# tinylab_09-03-16.net
KiCad netlist of a schematic drawn in EAGLE
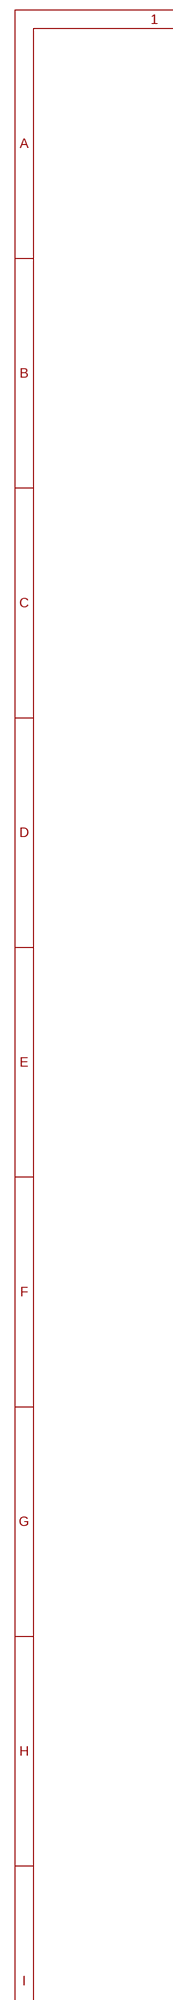
[diagram p0: schematic, sheet 1, part 1 of 2]
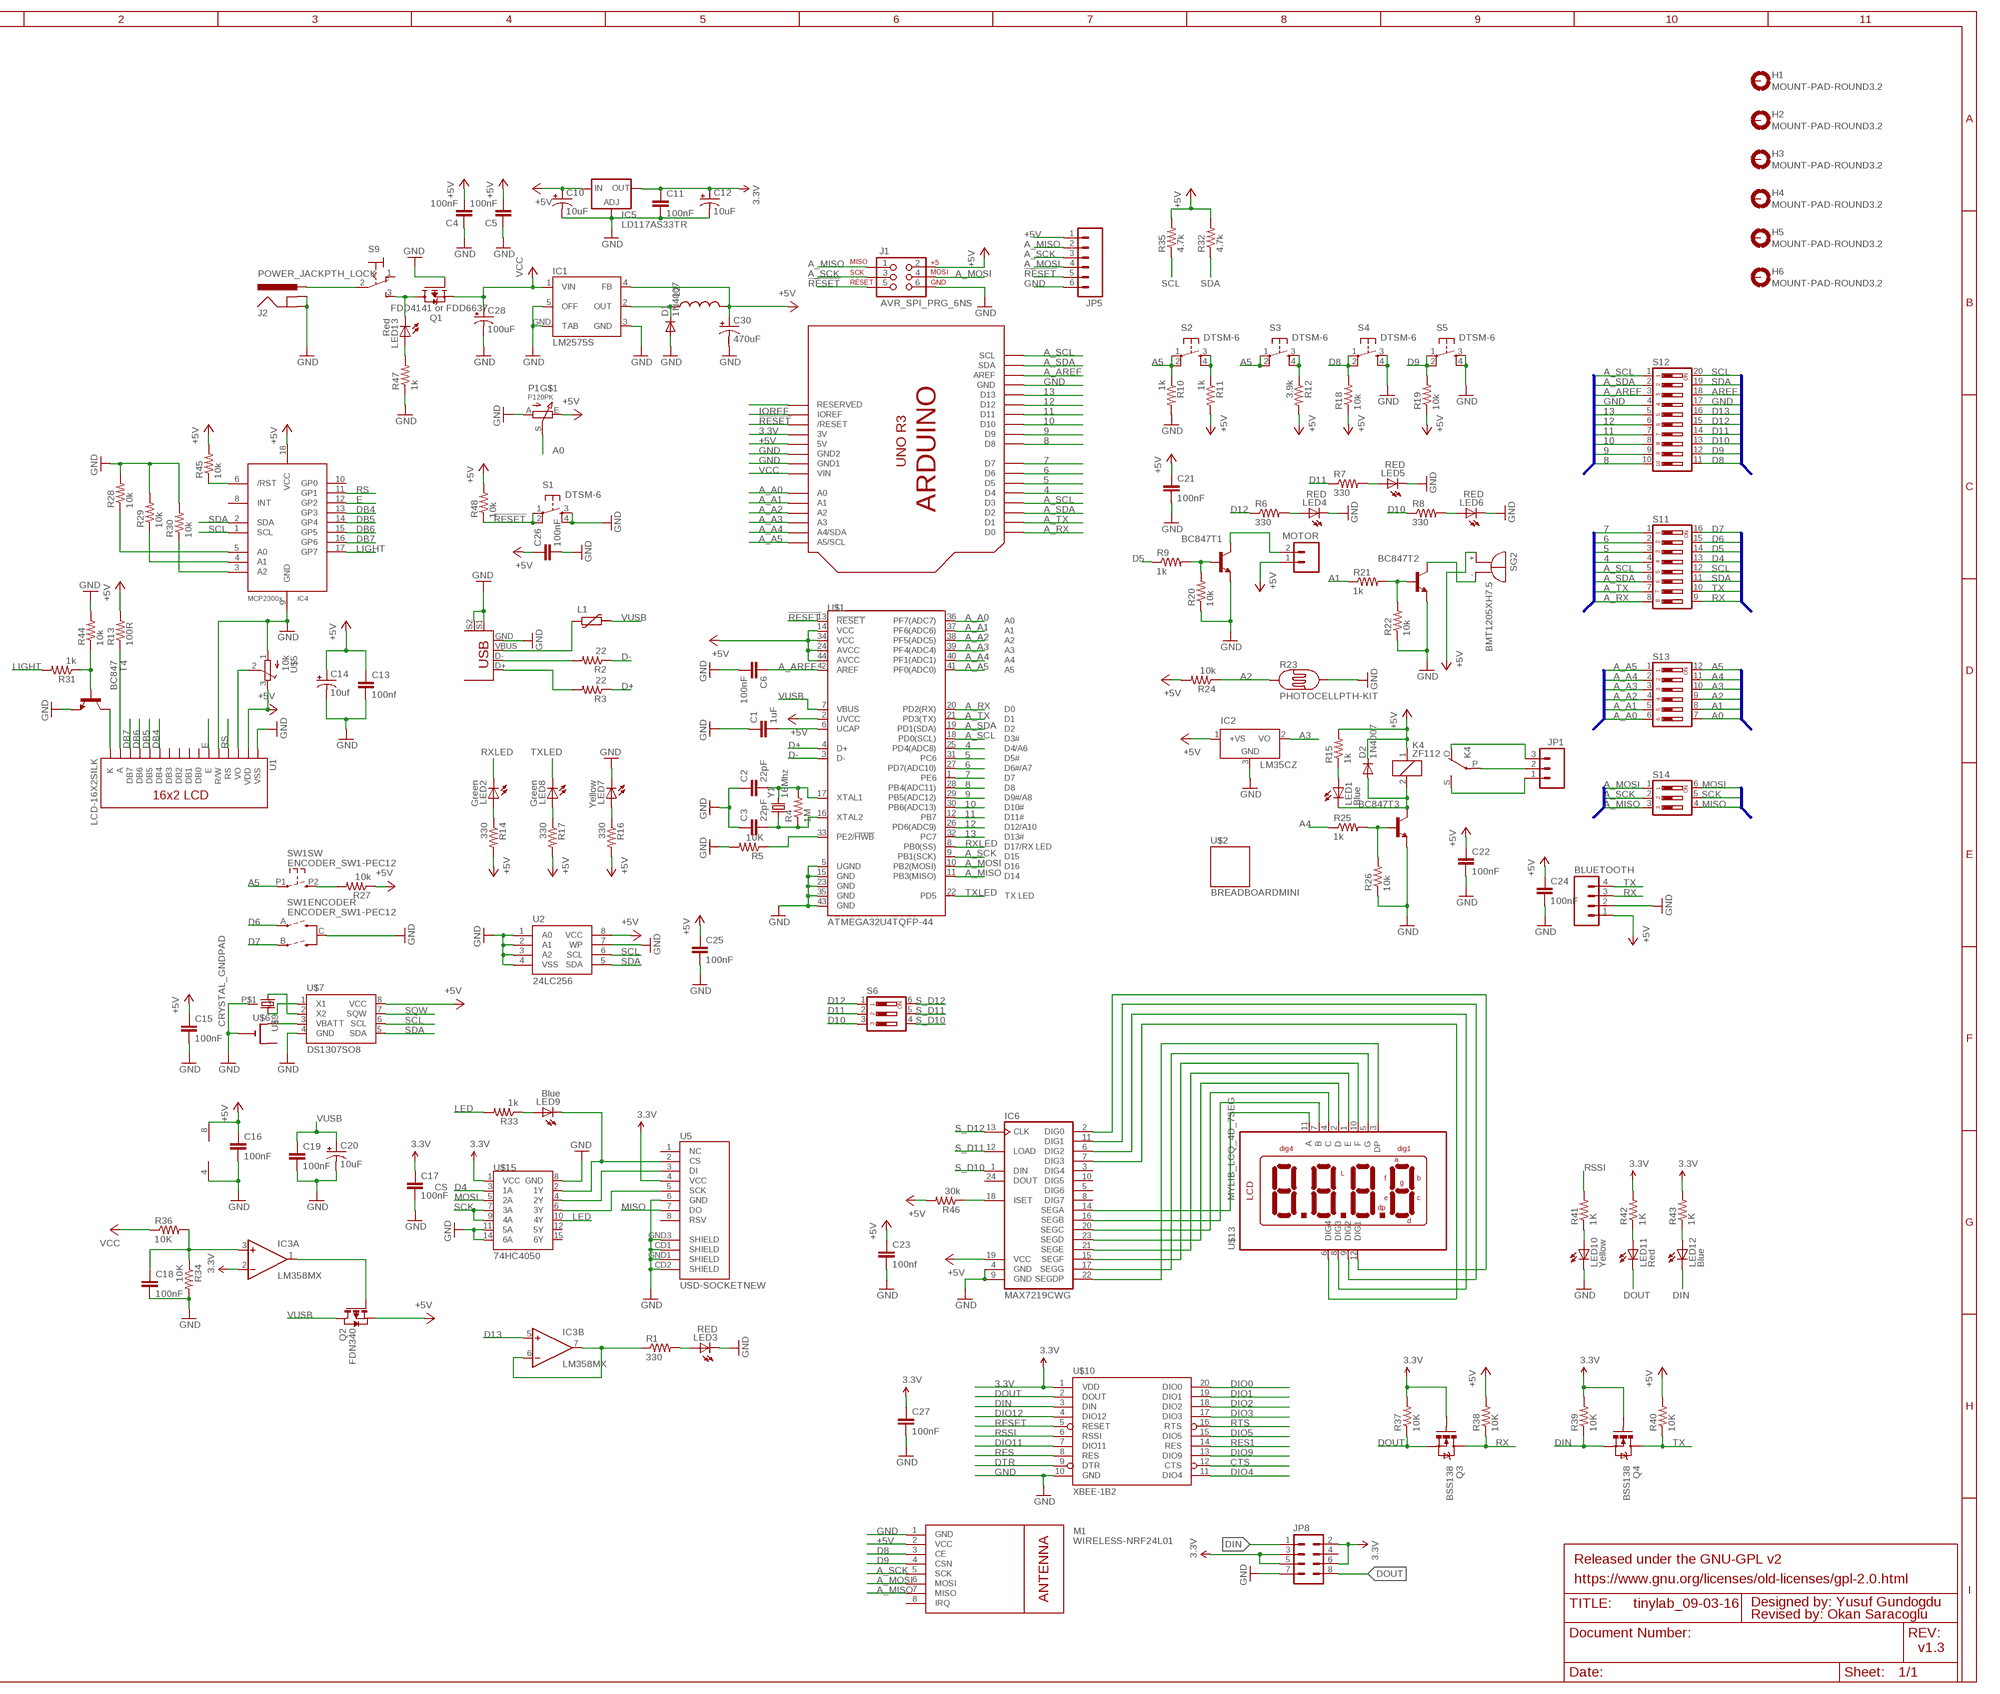
[diagram p1: schematic, sheet 1, part 2 of 2]

(export (version "E")
  (design (tool "Eeschema 10.0.6"))
  (components
    (comp (ref "BLUETOOTH")
      (value "M04PTH")
      (footprint "eagle-import:1X04")
      (libsource (lib "eagle-import") (part "M04PTH"))
    )
    (comp (ref "C1")
      (value "1uF")
      (footprint "eagle-import:1206")
      (libsource (lib "eagle-import") (part "CAP1206"))
    )
    (comp (ref "C2")
      (value "22pF")
      (footprint "eagle-import:0805")
      (libsource (lib "eagle-import") (part "CAP0805"))
    )
    (comp (ref "C3")
      (value "22pF")
      (footprint "eagle-import:0805")
      (libsource (lib "eagle-import") (part "CAP0805"))
    )
    (comp (ref "C4")
      (value "100nF")
      (footprint "eagle-import:0805")
      (libsource (lib "eagle-import") (part "CAP0805"))
    )
    (comp (ref "C5")
      (value "100nF")
      (footprint "eagle-import:0805")
      (libsource (lib "eagle-import") (part "CAP0805"))
    )
    (comp (ref "C6")
      (value "100nF")
      (footprint "eagle-import:0805")
      (libsource (lib "eagle-import") (part "CAP0805"))
    )
    (comp (ref "C10")
      (value "10uF")
      (footprint "eagle-import:EIA3216")
      (libsource (lib "eagle-import") (part "CAP_POL1206"))
    )
    (comp (ref "C11")
      (value "100nF")
      (footprint "eagle-import:0805")
      (libsource (lib "eagle-import") (part "CAP0805"))
    )
    (comp (ref "C12")
      (value "10uF")
      (footprint "eagle-import:EIA3216")
      (libsource (lib "eagle-import") (part "CAP_POL1206"))
    )
    (comp (ref "C13")
      (value "100nf")
      (footprint "eagle-import:0805")
      (libsource (lib "eagle-import") (part "CAP0805"))
    )
    (comp (ref "C14")
      (value "10uf")
      (footprint "eagle-import:EIA3216")
      (libsource (lib "eagle-import") (part "CAP_POL1206"))
    )
    (comp (ref "C15")
      (value "100nF")
      (footprint "eagle-import:0805")
      (libsource (lib "eagle-import") (part "CAP0805"))
    )
    (comp (ref "C16")
      (value "100nF")
      (footprint "eagle-import:0805")
      (libsource (lib "eagle-import") (part "CAP0805"))
    )
    (comp (ref "C17")
      (value "100nF")
      (footprint "eagle-import:0805")
      (libsource (lib "eagle-import") (part "CAP0805"))
    )
    (comp (ref "C18")
      (value "100nF")
      (footprint "eagle-import:0805")
      (libsource (lib "eagle-import") (part "CAP0805"))
    )
    (comp (ref "C19")
      (value "100nF")
      (footprint "eagle-import:0805")
      (libsource (lib "eagle-import") (part "CAP0805"))
    )
    (comp (ref "C20")
      (value "10uF")
      (footprint "eagle-import:EIA3216")
      (libsource (lib "eagle-import") (part "CAP_POL1206"))
    )
    (comp (ref "C21")
      (value "100nF")
      (footprint "eagle-import:0805")
      (libsource (lib "eagle-import") (part "CAP0805"))
    )
    (comp (ref "C22")
      (value "100nF")
      (footprint "eagle-import:0805")
      (libsource (lib "eagle-import") (part "CAP0805"))
    )
    (comp (ref "C23")
      (value "100nf")
      (footprint "eagle-import:0805")
      (libsource (lib "eagle-import") (part "CAP0805"))
    )
    (comp (ref "C24")
      (value "100nF")
      (footprint "eagle-import:0805")
      (libsource (lib "eagle-import") (part "CAP0805"))
    )
    (comp (ref "C25")
      (value "100nF")
      (footprint "eagle-import:0805")
      (libsource (lib "eagle-import") (part "CAP0805"))
    )
    (comp (ref "C26")
      (value "100nF")
      (footprint "eagle-import:0805")
      (libsource (lib "eagle-import") (part "CAP0805"))
    )
    (comp (ref "C27")
      (value "100nF")
      (footprint "eagle-import:0805")
      (libsource (lib "eagle-import") (part "CAP0805"))
    )
    (comp (ref "C28")
      (value "100uF")
      (footprint "eagle-import:NIPPON_F80")
      (libsource (lib "eagle-import") (part "CAP_POLF80"))
    )
    (comp (ref "C30")
      (value "470uF")
      (footprint "eagle-import:PANASONIC_G")
      (libsource (lib "eagle-import") (part "CAP_POLG"))
    )
    (comp (ref "D1")
      (value "1N4007")
      (footprint "eagle-import:SMA-DIODE_ALT")
      (libsource (lib "eagle-import") (part "DIODESMA-ALT"))
    )
    (comp (ref "D2")
      (value "1N4007")
      (footprint "eagle-import:SMA-DIODE_ALT")
      (libsource (lib "eagle-import") (part "DIODESMA-ALT"))
    )
    (comp (ref "H1")
      (value "MOUNT-PAD-ROUND3.2")
      (footprint "eagle-import:3,2-PAD")
      (libsource (lib "eagle-import") (part "MOUNT-PAD-ROUND3.2"))
    )
    (comp (ref "H2")
      (value "MOUNT-PAD-ROUND3.2")
      (footprint "eagle-import:3,2-PAD")
      (libsource (lib "eagle-import") (part "MOUNT-PAD-ROUND3.2"))
    )
    (comp (ref "H3")
      (value "MOUNT-PAD-ROUND3.2")
      (footprint "eagle-import:3,2-PAD")
      (libsource (lib "eagle-import") (part "MOUNT-PAD-ROUND3.2"))
    )
    (comp (ref "H4")
      (value "MOUNT-PAD-ROUND3.2")
      (footprint "eagle-import:3,2-PAD")
      (libsource (lib "eagle-import") (part "MOUNT-PAD-ROUND3.2"))
    )
    (comp (ref "H5")
      (value "MOUNT-PAD-ROUND3.2")
      (footprint "eagle-import:3,2-PAD")
      (libsource (lib "eagle-import") (part "MOUNT-PAD-ROUND3.2"))
    )
    (comp (ref "H6")
      (value "MOUNT-PAD-ROUND3.2")
      (footprint "eagle-import:3,2-PAD")
      (libsource (lib "eagle-import") (part "MOUNT-PAD-ROUND3.2"))
    )
    (comp (ref "IC1")
      (value "LM2575S")
      (footprint "eagle-import:TO263-5")
      (libsource (lib "eagle-import") (part "LM2575S"))
    )
    (comp (ref "IC2")
      (value "LM35CZ")
      (footprint "eagle-import:TO92")
      (libsource (lib "eagle-import") (part "LM35CZ"))
    )
    (comp (ref "IC3")
      (value "LM358MX")
      (footprint "eagle-import:SO08")
      (libsource (lib "eagle-import") (part "LM358MX"))
    )
    (comp (ref "IC4")
      (value "MCP2300X/SO")
      (footprint "eagle-import:SO18W")
      (libsource (lib "eagle-import") (part "MCP2300X/SO"))
    )
    (comp (ref "IC5")
      (value "LD117AS33TR")
      (footprint "eagle-import:SOT223")
      (libsource (lib "eagle-import") (part "LD117A?S33TR"))
    )
    (comp (ref "IC6")
      (value "MAX7219CWG")
      (footprint "eagle-import:SO24W")
      (libsource (lib "eagle-import") (part "MAX7219WGC"))
    )
    (comp (ref "J1")
      (value "AVR_SPI_PRG_6NS")
      (footprint "eagle-import:2X3-NS")
      (libsource (lib "eagle-import") (part "AVR_SPI_PRG_6NS"))
    )
    (comp (ref "J2")
      (value "POWER_JACKPTH_LOCK")
      (footprint "eagle-import:POWER_JACK_PTH_LOCK")
      (libsource (lib "eagle-import") (part "POWER_JACKPTH_LOCK"))
    )
    (comp (ref "JP1")
      (value "M03-SCREW-5MM")
      (footprint "eagle-import:SCREWTERMINAL-5MM-3")
      (libsource (lib "eagle-import") (part "M03-SCREW-5MM"))
    )
    (comp (ref "JP5")
      (value "M06SIP")
      (footprint "eagle-import:1X06")
      (libsource (lib "eagle-import") (part "M06SIP"))
    )
    (comp (ref "JP8")
      (value "M04X2")
      (footprint "eagle-import:2X4")
      (libsource (lib "eagle-import") (part "M04X2"))
    )
    (comp (ref "K4")
      (value "ZF112")
      (footprint "eagle-import:ZF112")
      (libsource (lib "eagle-import") (part "ZF112"))
    )
    (comp (ref "L1")
      (value "FUSE_PTC-0805")
      (footprint "eagle-import:PTC0805")
      (libsource (lib "eagle-import") (part "FUSE_PTC-0805"))
    )
    (comp (ref "L2")
      (value "INDUCTORPWR")
      (footprint "eagle-import:CDRH125")
      (libsource (lib "eagle-import") (part "INDUCTORPWR"))
    )
    (comp (ref "LED1")
      (value "Blue")
      (footprint "eagle-import:CHIPLED_0805")
      (libsource (lib "eagle-import") (part "LEDCHIPLED_0805"))
    )
    (comp (ref "LED2")
      (value "Green")
      (footprint "eagle-import:CHIPLED_0805")
      (libsource (lib "eagle-import") (part "LEDCHIPLED_0805"))
    )
    (comp (ref "LED3")
      (value "RED")
      (footprint "eagle-import:LED5MM")
      (libsource (lib "eagle-import") (part "LED5MM"))
    )
    (comp (ref "LED4")
      (value "RED")
      (footprint "eagle-import:LED5MM")
      (libsource (lib "eagle-import") (part "LED5MM"))
    )
    (comp (ref "LED5")
      (value "RED")
      (footprint "eagle-import:LED5MM")
      (libsource (lib "eagle-import") (part "LED5MM"))
    )
    (comp (ref "LED6")
      (value "RED")
      (footprint "eagle-import:LED5MM")
      (libsource (lib "eagle-import") (part "LED5MM"))
    )
    (comp (ref "LED7")
      (value "Yellow")
      (footprint "eagle-import:CHIPLED_0805")
      (libsource (lib "eagle-import") (part "LEDCHIPLED_0805"))
    )
    (comp (ref "LED8")
      (value "Green")
      (footprint "eagle-import:CHIPLED_0805")
      (libsource (lib "eagle-import") (part "LEDCHIPLED_0805"))
    )
    (comp (ref "LED9")
      (value "Blue")
      (footprint "eagle-import:CHIPLED_0805")
      (libsource (lib "eagle-import") (part "LEDCHIPLED_0805"))
    )
    (comp (ref "LED10")
      (value "Yellow")
      (footprint "eagle-import:CHIPLED_0805")
      (libsource (lib "eagle-import") (part "LEDCHIPLED_0805"))
    )
    (comp (ref "LED11")
      (value "Red")
      (footprint "eagle-import:CHIPLED_0805")
      (libsource (lib "eagle-import") (part "LEDCHIPLED_0805"))
    )
    (comp (ref "LED12")
      (value "Blue")
      (footprint "eagle-import:CHIPLED_0805")
      (libsource (lib "eagle-import") (part "LEDCHIPLED_0805"))
    )
    (comp (ref "LED13")
      (value "Red")
      (footprint "eagle-import:CHIPLED_0805")
      (libsource (lib "eagle-import") (part "LEDCHIPLED_0805"))
    )
    (comp (ref "M1")
      (value "WIRELESS-NRF24L01")
      (footprint "eagle-import:WIRELESS-NRF24L01")
      (libsource (lib "eagle-import") (part "WIRELESS-NRF24L01"))
    )
    (comp (ref "MOTOR")
      (value "M023.5MM")
      (footprint "eagle-import:SCREWTERMINAL-3.5MM-2")
      (libsource (lib "eagle-import") (part "M023.5MM"))
    )
    (comp (ref "P1")
      (value "P120PK")
      (footprint "eagle-import:P120PK")
      (libsource (lib "eagle-import") (part "P120PK"))
    )
    (comp (ref "Q1")
      (value "FDD4141 or FDD6637")
      (footprint "eagle-import:TO252")
      (libsource (lib "eagle-import") (part "FDD4141TO252"))
    )
    (comp (ref "Q2")
      (value "FDN340")
      (footprint "eagle-import:SOT-23")
      (libsource (lib "eagle-import") (part "PMOSSOT23"))
    )
    (comp (ref "Q3")
      (value "BSS138")
      (footprint "eagle-import:SOT23-3")
      (libsource (lib "eagle-import") (part "MOSFET-NCHANNELSMD"))
    )
    (comp (ref "Q4")
      (value "BSS138")
      (footprint "eagle-import:SOT23-3")
      (libsource (lib "eagle-import") (part "MOSFET-NCHANNELSMD"))
    )
    (comp (ref "R1")
      (value "330")
      (footprint "eagle-import:0805")
      (libsource (lib "eagle-import") (part "RESISTOR0805-RES"))
    )
    (comp (ref "R2")
      (value "22")
      (footprint "eagle-import:0805")
      (libsource (lib "eagle-import") (part "RESISTOR0805-RES"))
    )
    (comp (ref "R3")
      (value "22")
      (footprint "eagle-import:0805")
      (libsource (lib "eagle-import") (part "RESISTOR0805-RES"))
    )
    (comp (ref "R4")
      (value "1M")
      (footprint "eagle-import:0805")
      (libsource (lib "eagle-import") (part "RESISTOR0805-RES"))
    )
    (comp (ref "R5")
      (value "10K")
      (footprint "eagle-import:0805")
      (libsource (lib "eagle-import") (part "RESISTOR0805-RES"))
    )
    (comp (ref "R6")
      (value "330")
      (footprint "eagle-import:0805")
      (libsource (lib "eagle-import") (part "RESISTOR0805-RES"))
    )
    (comp (ref "R7")
      (value "330")
      (footprint "eagle-import:0805")
      (libsource (lib "eagle-import") (part "RESISTOR0805-RES"))
    )
    (comp (ref "R8")
      (value "330")
      (footprint "eagle-import:0805")
      (libsource (lib "eagle-import") (part "RESISTOR0805-RES"))
    )
    (comp (ref "R9")
      (value "1k")
      (footprint "eagle-import:0805")
      (libsource (lib "eagle-import") (part "RESISTOR0805-RES"))
    )
    (comp (ref "R10")
      (value "1k")
      (footprint "eagle-import:0805")
      (libsource (lib "eagle-import") (part "RESISTOR0805-RES"))
    )
    (comp (ref "R11")
      (value "1k")
      (footprint "eagle-import:0805")
      (libsource (lib "eagle-import") (part "RESISTOR0805-RES"))
    )
    (comp (ref "R12")
      (value "3.9k")
      (footprint "eagle-import:0805")
      (libsource (lib "eagle-import") (part "RESISTOR0805-RES"))
    )
    (comp (ref "R13")
      (value "100R")
      (footprint "eagle-import:0805")
      (libsource (lib "eagle-import") (part "RESISTOR0805-RES"))
    )
    (comp (ref "R14")
      (value "330")
      (footprint "eagle-import:0805")
      (libsource (lib "eagle-import") (part "RESISTOR0805-RES"))
    )
    (comp (ref "R15")
      (value "1k")
      (footprint "eagle-import:0805")
      (libsource (lib "eagle-import") (part "RESISTOR0805-RES"))
    )
    (comp (ref "R16")
      (value "330")
      (footprint "eagle-import:0805")
      (libsource (lib "eagle-import") (part "RESISTOR0805-RES"))
    )
    (comp (ref "R17")
      (value "330")
      (footprint "eagle-import:0805")
      (libsource (lib "eagle-import") (part "RESISTOR0805-RES"))
    )
    (comp (ref "R18")
      (value "10k")
      (footprint "eagle-import:0805")
      (libsource (lib "eagle-import") (part "RESISTOR0805-RES"))
    )
    (comp (ref "R19")
      (value "10k")
      (footprint "eagle-import:0805")
      (libsource (lib "eagle-import") (part "RESISTOR0805-RES"))
    )
    (comp (ref "R20")
      (value "10k")
      (footprint "eagle-import:0805")
      (libsource (lib "eagle-import") (part "RESISTOR0805-RES"))
    )
    (comp (ref "R21")
      (value "1k")
      (footprint "eagle-import:0805")
      (libsource (lib "eagle-import") (part "RESISTOR0805-RES"))
    )
    (comp (ref "R22")
      (value "10k")
      (footprint "eagle-import:0805")
      (libsource (lib "eagle-import") (part "RESISTOR0805-RES"))
    )
    (comp (ref "R23")
      (value "PHOTOCELLPTH-KIT")
      (footprint "eagle-import:PHOTOCELL-KIT")
      (libsource (lib "eagle-import") (part "PHOTOCELLPTH-KIT"))
    )
    (comp (ref "R24")
      (value "10k")
      (footprint "eagle-import:0805")
      (libsource (lib "eagle-import") (part "RESISTOR0805-RES"))
    )
    (comp (ref "R25")
      (value "1k")
      (footprint "eagle-import:0805")
      (libsource (lib "eagle-import") (part "RESISTOR0805-RES"))
    )
    (comp (ref "R26")
      (value "10k")
      (footprint "eagle-import:0805")
      (libsource (lib "eagle-import") (part "RESISTOR0805-RES"))
    )
    (comp (ref "R27")
      (value "10k")
      (footprint "eagle-import:0805")
      (libsource (lib "eagle-import") (part "RESISTOR0805-RES"))
    )
    (comp (ref "R28")
      (value "10k")
      (footprint "eagle-import:0805")
      (libsource (lib "eagle-import") (part "RESISTOR0805-RES"))
    )
    (comp (ref "R29")
      (value "10k")
      (footprint "eagle-import:0805")
      (libsource (lib "eagle-import") (part "RESISTOR0805-RES"))
    )
    (comp (ref "R30")
      (value "10k")
      (footprint "eagle-import:0805")
      (libsource (lib "eagle-import") (part "RESISTOR0805-RES"))
    )
    (comp (ref "R31")
      (value "1k")
      (footprint "eagle-import:0805")
      (libsource (lib "eagle-import") (part "RESISTOR0805-RES"))
    )
    (comp (ref "R32")
      (value "4.7k")
      (footprint "eagle-import:0805")
      (libsource (lib "eagle-import") (part "RESISTOR0805-RES"))
    )
    (comp (ref "R33")
      (value "1k")
      (footprint "eagle-import:0805")
      (libsource (lib "eagle-import") (part "RESISTOR0805-RES"))
    )
    (comp (ref "R34")
      (value "10K")
      (footprint "eagle-import:0805")
      (libsource (lib "eagle-import") (part "RESISTOR0805-RES"))
    )
    (comp (ref "R35")
      (value "4.7k")
      (footprint "eagle-import:0805")
      (libsource (lib "eagle-import") (part "RESISTOR0805-RES"))
    )
    (comp (ref "R36")
      (value "10K")
      (footprint "eagle-import:0805")
      (libsource (lib "eagle-import") (part "RESISTOR0805-RES"))
    )
    (comp (ref "R37")
      (value "10K")
      (footprint "eagle-import:0805")
      (libsource (lib "eagle-import") (part "RESISTOR0805-RES"))
    )
    (comp (ref "R38")
      (value "10K")
      (footprint "eagle-import:0805")
      (libsource (lib "eagle-import") (part "RESISTOR0805-RES"))
    )
    (comp (ref "R39")
      (value "10K")
      (footprint "eagle-import:0805")
      (libsource (lib "eagle-import") (part "RESISTOR0805-RES"))
    )
    (comp (ref "R40")
      (value "10K")
      (footprint "eagle-import:0805")
      (libsource (lib "eagle-import") (part "RESISTOR0805-RES"))
    )
    (comp (ref "R41")
      (value "1K")
      (footprint "eagle-import:0805")
      (libsource (lib "eagle-import") (part "RESISTOR0805-RES"))
    )
    (comp (ref "R42")
      (value "1K")
      (footprint "eagle-import:0805")
      (libsource (lib "eagle-import") (part "RESISTOR0805-RES"))
    )
    (comp (ref "R43")
      (value "1K")
      (footprint "eagle-import:0805")
      (libsource (lib "eagle-import") (part "RESISTOR0805-RES"))
    )
    (comp (ref "R44")
      (value "10k")
      (footprint "eagle-import:0805")
      (libsource (lib "eagle-import") (part "RESISTOR0805-RES"))
    )
    (comp (ref "R45")
      (value "10k")
      (footprint "eagle-import:0805")
      (libsource (lib "eagle-import") (part "RESISTOR0805-RES"))
    )
    (comp (ref "R46")
      (value "30k")
      (footprint "eagle-import:0805")
      (libsource (lib "eagle-import") (part "RESISTOR0805-RES"))
    )
    (comp (ref "R47")
      (value "1k")
      (footprint "eagle-import:0805")
      (libsource (lib "eagle-import") (part "RESISTOR0805-RES"))
    )
    (comp (ref "R48")
      (value "10k")
      (footprint "eagle-import:0805")
      (libsource (lib "eagle-import") (part "RESISTOR0805-RES"))
    )
    (comp (ref "S1")
      (value "DTSM-6")
      (footprint "eagle-import:DTSM-6")
      (libsource (lib "eagle-import") (part "DTSM-6"))
    )
    (comp (ref "S2")
      (value "DTSM-6")
      (footprint "eagle-import:DTSM-6")
      (libsource (lib "eagle-import") (part "DTSM-6"))
    )
    (comp (ref "S3")
      (value "DTSM-6")
      (footprint "eagle-import:DTSM-6")
      (libsource (lib "eagle-import") (part "DTSM-6"))
    )
    (comp (ref "S4")
      (value "DTSM-6")
      (footprint "eagle-import:DTSM-6")
      (libsource (lib "eagle-import") (part "DTSM-6"))
    )
    (comp (ref "S5")
      (value "DTSM-6")
      (footprint "eagle-import:DTSM-6")
      (libsource (lib "eagle-import") (part "DTSM-6"))
    )
    (comp (ref "S6")
      (value "DIP03YL")
      (footprint "eagle-import:DIP03YL")
      (fields (field (name "OC_FARNELL") "unknown") (field (name "OC_NEWARK") "unknown"))
      (libsource (lib "eagle-import") (part "DIP03YL"))
    )
    (comp (ref "S9")
      (value "M9040P")
      (footprint "eagle-import:M9040P")
      (libsource (lib "eagle-import") (part "M9040P"))
    )
    (comp (ref "S11")
      (value "DIP08YL")
      (footprint "eagle-import:DIP08YL")
      (libsource (lib "eagle-import") (part "DIP08YL"))
    )
    (comp (ref "S12")
      (value "DIP10YL")
      (footprint "eagle-import:DIP10YL")
      (libsource (lib "eagle-import") (part "DIP10YL"))
    )
    (comp (ref "S13")
      (value "DIP06YL")
      (footprint "eagle-import:DIP06YL")
      (libsource (lib "eagle-import") (part "DIP06YL"))
    )
    (comp (ref "S14")
      (value "DIP03YL")
      (footprint "eagle-import:DIP03YL")
      (libsource (lib "eagle-import") (part "DIP03YL"))
    )
    (comp (ref "SG2")
      (value "BMT1205XH7.5")
      (footprint "eagle-import:BMT1205XH7.5")
      (libsource (lib "eagle-import") (part "BMT1205XH7.5"))
    )
    (comp (ref "SW1")
      (value "ENCODER_SW1-PEC12")
      (footprint "eagle-import:PEC12_INCREMENTAL_ENCODER")
      (libsource (lib "eagle-import") (part "ENCODER_SW1-PEC12"))
    )
    (comp (ref "T1")
      (value "BC847")
      (footprint "eagle-import:SOT23-BEC")
      (libsource (lib "eagle-import") (part "-NPN-SOT23-BECMMBT2222ALT1"))
    )
    (comp (ref "T2")
      (value "BC847")
      (footprint "eagle-import:SOT23-BEC")
      (libsource (lib "eagle-import") (part "-NPN-SOT23-BECMMBT2222ALT1"))
    )
    (comp (ref "T3")
      (value "BC847")
      (footprint "eagle-import:SOT23-BEC")
      (libsource (lib "eagle-import") (part "-NPN-SOT23-BECMMBT2222ALT1"))
    )
    (comp (ref "T4")
      (value "BC847")
      (footprint "eagle-import:SOT23-BEC")
      (libsource (lib "eagle-import") (part "-NPN-SOT23-BECMMBT2222ALT1"))
    )
    (comp (ref "U$1")
      (value "ATMEGA32U4TQFP-44")
      (footprint "eagle-import:TQFP44")
      (libsource (lib "eagle-import") (part "ATMEGA32U4TQFP-44"))
    )
    (comp (ref "U$2")
      (value "BREADBOARDMINI")
      (footprint "eagle-import:BREADBOARD-MINI")
      (libsource (lib "eagle-import") (part "BREADBOARDMINI"))
    )
    (comp (ref "U$3")
      (value "USB+SHIELD")
      (footprint "eagle-import:USB-B-PTH")
      (libsource (lib "eagle-import") (part "USB+SHIELD"))
    )
    (comp (ref "U$4")
      (value "UNO_R3")
      (footprint "eagle-import:UNO_R3")
      (libsource (lib "eagle-import") (part "UNO_R3"))
    )
    (comp (ref "U$5")
      (value "10k")
      (footprint "eagle-import:TC33X")
      (libsource (lib "eagle-import") (part "TRIMPOTTC33X"))
    )
    (comp (ref "U$6")
      (value "CR1220SMT")
      (footprint "eagle-import:CR1220-SMD")
      (libsource (lib "eagle-import") (part "CR1220SMT"))
    )
    (comp (ref "U$7")
      (value "DS1307SO8")
      (footprint "eagle-import:SO08")
      (libsource (lib "eagle-import") (part "DS1307SO8"))
    )
    (comp (ref "U$9")
      (value "CRYSTAL_GNDPAD")
      (footprint "eagle-import:TC38H_GNDPAD")
      (libsource (lib "eagle-import") (part "CRYSTAL_GNDPAD"))
    )
    (comp (ref "U$10")
      (value "XBEE-1B2")
      (footprint "eagle-import:XBEE-SILK")
      (libsource (lib "eagle-import") (part "XBEE-1B2"))
    )
    (comp (ref "U$13")
      (value "MYLIB_LCQ_4D_7SEG")
      (footprint "eagle-import:MYLIB_LDQ_4D_7SEG")
      (libsource (lib "eagle-import") (part "MYLIB_LCQ_4D_7SEG"))
    )
    (comp (ref "U$15")
      (value "74HC4050")
      (footprint "eagle-import:SO016")
      (libsource (lib "eagle-import") (part "HEX_CONVERTER"))
    )
    (comp (ref "U1")
      (value "LCD-16X2SILK")
      (footprint "eagle-import:LCD-16X2")
      (libsource (lib "eagle-import") (part "LCD-16X2SILK"))
    )
    (comp (ref "U2")
      (value "24LC256")
      (footprint "eagle-import:SO08")
      (libsource (lib "eagle-import") (part "EEPROM-I2CSMD"))
    )
    (comp (ref "U5")
      (value "USD-SOCKETNEW")
      (footprint "eagle-import:MICRO-SD-SOCKET-PP")
      (libsource (lib "eagle-import") (part "USD-SOCKETNEW"))
    )
    (comp (ref "Y1")
      (value "16Mhz")
      (footprint "eagle-import:CRYSTAL-SMD-5X3")
      (libsource (lib "eagle-import") (part "CRYSTAL5X3"))
    )
  )
  (nets
    (net (code "1") (name "+5V") (class "Default")
      (node (ref "BLUETOOTH") (pin "1") (pinfunction "1_1") (pintype "passive"))
      (node (ref "C10") (pin "A") (pinfunction "+_A") (pintype "passive"))
      (node (ref "C13") (pin "1") (pinfunction "1_1") (pintype "passive"))
      (node (ref "C14") (pin "A") (pinfunction "+_A") (pintype "passive"))
      (node (ref "C15") (pin "1") (pinfunction "1_1") (pintype "passive"))
      (node (ref "C16") (pin "1") (pinfunction "1_1") (pintype "passive"))
      (node (ref "C21") (pin "1") (pinfunction "1_1") (pintype "passive"))
      (node (ref "C22") (pin "1") (pinfunction "1_1") (pintype "passive"))
      (node (ref "C23") (pin "1") (pinfunction "1_1") (pintype "passive"))
      (node (ref "C24") (pin "1") (pinfunction "1_1") (pintype "passive"))
      (node (ref "C25") (pin "1") (pinfunction "1_1") (pintype "passive"))
      (node (ref "C26") (pin "1") (pinfunction "1_1") (pintype "passive"))
      (node (ref "C30") (pin "+") (pinfunction "+_+") (pintype "passive"))
      (node (ref "C4") (pin "2") (pinfunction "2_2") (pintype "passive"))
      (node (ref "C5") (pin "2") (pinfunction "2_2") (pintype "passive"))
      (node (ref "D2") (pin "C") (pinfunction "C_C") (pintype "passive"))
      (node (ref "IC1") (pin "4") (pinfunction "FB_4") (pintype "input"))
      (node (ref "IC2") (pin "1") (pinfunction "+VS_1") (pintype "input"))
      (node (ref "IC3") (pin "8") (pinfunction "V+_8") (pintype "power_in"))
      (node (ref "IC4") (pin "18") (pinfunction "VCC_18") (pintype "power_in"))
      (node (ref "IC5") (pin "3") (pinfunction "IN_3") (pintype "input"))
      (node (ref "IC6") (pin "19") (pinfunction "VCC_19") (pintype "power_in"))
      (node (ref "J1") (pin "2") (pinfunction "2_2") (pintype "passive"))
      (node (ref "JP5") (pin "1") (pinfunction "1_1") (pintype "passive"))
      (node (ref "K4") (pin "1") (pinfunction "1_1") (pintype "passive"))
      (node (ref "L2") (pin "2") (pinfunction "2_2") (pintype "passive"))
      (node (ref "M1") (pin "2") (pinfunction "VCC_2") (pintype "power_in"))
      (node (ref "MOTOR") (pin "1") (pinfunction "1_1") (pintype "passive"))
      (node (ref "P1") (pin "E") (pinfunction "E_E") (pintype "passive"))
      (node (ref "Q2") (pin "2") (pinfunction "S_2") (pintype "passive"))
      (node (ref "R11") (pin "2") (pinfunction "2_2") (pintype "passive"))
      (node (ref "R12") (pin "2") (pinfunction "2_2") (pintype "passive"))
      (node (ref "R13") (pin "2") (pinfunction "2_2") (pintype "passive"))
      (node (ref "R14") (pin "2") (pinfunction "2_2") (pintype "passive"))
      (node (ref "R15") (pin "2") (pinfunction "2_2") (pintype "passive"))
      (node (ref "R16") (pin "2") (pinfunction "2_2") (pintype "passive"))
      (node (ref "R17") (pin "2") (pinfunction "2_2") (pintype "passive"))
      (node (ref "R18") (pin "1") (pinfunction "1_1") (pintype "passive"))
      (node (ref "R19") (pin "1") (pinfunction "1_1") (pintype "passive"))
      (node (ref "R24") (pin "2") (pinfunction "2_2") (pintype "passive"))
      (node (ref "R27") (pin "1") (pinfunction "1_1") (pintype "passive"))
      (node (ref "R32") (pin "2") (pinfunction "2_2") (pintype "passive"))
      (node (ref "R35") (pin "2") (pinfunction "2_2") (pintype "passive"))
      (node (ref "R38") (pin "2") (pinfunction "2_2") (pintype "passive"))
      (node (ref "R40") (pin "2") (pinfunction "2_2") (pintype "passive"))
      (node (ref "R45") (pin "2") (pinfunction "2_2") (pintype "passive"))
      (node (ref "R46") (pin "2") (pinfunction "2_2") (pintype "passive"))
      (node (ref "R48") (pin "2") (pinfunction "2_2") (pintype "passive"))
      (node (ref "SG2") (pin "+") (pinfunction "+_+") (pintype "passive"))
      (node (ref "U$1") (pin "14") (pinfunction "VCC_14") (pintype "bidirectional"))
      (node (ref "U$1") (pin "2") (pinfunction "UVCC_2") (pintype "bidirectional"))
      (node (ref "U$1") (pin "24") (pinfunction "AVCC_24") (pintype "bidirectional"))
      (node (ref "U$1") (pin "34") (pinfunction "VCC_34") (pintype "bidirectional"))
      (node (ref "U$1") (pin "44") (pinfunction "AVCC_44") (pintype "bidirectional"))
      (node (ref "U$4") (pin "5V") (pinfunction "5V_5V") (pintype "power_in"))
      (node (ref "U$5") (pin "3") (pinfunction "E_3") (pintype "passive"))
      (node (ref "U$7") (pin "8") (pinfunction "VCC_8") (pintype "bidirectional"))
      (node (ref "U1") (pin "2") (pinfunction "VDD_2") (pintype "power_in"))
      (node (ref "U2") (pin "8") (pinfunction "VCC_8") (pintype "power_in"))
    )
    (net (code "2") (name "/4") (class "Default")
      (node (ref "S11") (pin "4") (pinfunction "4_4") (pintype "passive"))
      (node (ref "U$1") (pin "25") (pinfunction "PD4(ADC8)_25") (pintype "bidirectional"))
      (node (ref "U$4") (pin "D4") (pinfunction "D4_D4") (pintype "bidirectional"))
    )
    (net (code "3") (name "/5") (class "Default")
      (node (ref "S11") (pin "3") (pinfunction "3_3") (pintype "passive"))
      (node (ref "U$1") (pin "31") (pinfunction "PC6_31") (pintype "bidirectional"))
      (node (ref "U$4") (pin "D5") (pinfunction "D5_D5") (pintype "bidirectional"))
    )
    (net (code "4") (name "/6") (class "Default")
      (node (ref "S11") (pin "2") (pinfunction "2_2") (pintype "passive"))
      (node (ref "U$1") (pin "27") (pinfunction "PD7(ADC10)_27") (pintype "bidirectional"))
      (node (ref "U$4") (pin "D6") (pinfunction "D6_D6") (pintype "bidirectional"))
    )
    (net (code "5") (name "/7") (class "Default")
      (node (ref "S11") (pin "1") (pinfunction "1_1") (pintype "passive"))
      (node (ref "U$1") (pin "1") (pinfunction "PE6_1") (pintype "bidirectional"))
      (node (ref "U$4") (pin "D7") (pinfunction "D7_D7") (pintype "bidirectional"))
    )
    (net (code "6") (name "/8") (class "Default")
      (node (ref "S12") (pin "10") (pinfunction "10_10") (pintype "passive"))
      (node (ref "U$1") (pin "28") (pinfunction "PB4(ADC11)_28") (pintype "bidirectional"))
      (node (ref "U$4") (pin "D8") (pinfunction "D8_D8") (pintype "bidirectional"))
    )
    (net (code "7") (name "/9") (class "Default")
      (node (ref "S12") (pin "9") (pinfunction "9_9") (pintype "passive"))
      (node (ref "U$1") (pin "29") (pinfunction "PB5(ADC12)_29") (pintype "bidirectional"))
      (node (ref "U$4") (pin "D9") (pinfunction "D9_D9") (pintype "bidirectional"))
    )
    (net (code "8") (name "/10") (class "Default")
      (node (ref "S12") (pin "8") (pinfunction "8_8") (pintype "passive"))
      (node (ref "U$1") (pin "30") (pinfunction "PB6(ADC13)_30") (pintype "bidirectional"))
      (node (ref "U$4") (pin "D10") (pinfunction "D10_D10") (pintype "bidirectional"))
    )
    (net (code "9") (name "/11") (class "Default")
      (node (ref "S12") (pin "7") (pinfunction "7_7") (pintype "passive"))
      (node (ref "U$1") (pin "12") (pinfunction "PB7_12") (pintype "bidirectional"))
      (node (ref "U$4") (pin "D11") (pinfunction "D11_D11") (pintype "bidirectional"))
    )
    (net (code "10") (name "/12") (class "Default")
      (node (ref "S12") (pin "6") (pinfunction "6_6") (pintype "passive"))
      (node (ref "U$1") (pin "26") (pinfunction "PD6(ADC9)_26") (pintype "bidirectional"))
      (node (ref "U$4") (pin "D12") (pinfunction "D12_D12") (pintype "bidirectional"))
    )
    (net (code "11") (name "/13") (class "Default")
      (node (ref "S12") (pin "5") (pinfunction "5_5") (pintype "passive"))
      (node (ref "U$1") (pin "32") (pinfunction "PC7_32") (pintype "bidirectional"))
      (node (ref "U$4") (pin "D13") (pinfunction "D13_D13") (pintype "bidirectional"))
    )
    (net (code "12") (name "/A0") (class "Default")
      (node (ref "P1") (pin "S") (pinfunction "S_S") (pintype "passive"))
      (node (ref "S13") (pin "7") (pinfunction "7_7") (pintype "passive"))
    )
    (net (code "13") (name "/A1") (class "Default")
      (node (ref "R21") (pin "1") (pinfunction "1_1") (pintype "passive"))
      (node (ref "S13") (pin "8") (pinfunction "8_8") (pintype "passive"))
    )
    (net (code "14") (name "/A2") (class "Default")
      (node (ref "R23") (pin "1") (pinfunction "P$1_1") (pintype "bidirectional"))
      (node (ref "R24") (pin "1") (pinfunction "1_1") (pintype "passive"))
      (node (ref "S13") (pin "9") (pinfunction "9_9") (pintype "passive"))
    )
    (net (code "15") (name "/A3") (class "Default")
      (node (ref "IC2") (pin "2") (pinfunction "VO_2") (pintype "input"))
      (node (ref "S13") (pin "10") (pinfunction "10_10") (pintype "passive"))
    )
    (net (code "16") (name "/A4") (class "Default")
      (node (ref "R25") (pin "1") (pinfunction "1_1") (pintype "passive"))
      (node (ref "S13") (pin "11") (pinfunction "11_11") (pintype "passive"))
    )
    (net (code "17") (name "/A5") (class "Default")
      (node (ref "R10") (pin "1") (pinfunction "1_1") (pintype "passive"))
      (node (ref "S13") (pin "12") (pinfunction "12_12") (pintype "passive"))
      (node (ref "S2") (pin "1") (pinfunction "1_1") (pintype "passive"))
      (node (ref "S2") (pin "2") (pinfunction "2_2") (pintype "passive"))
      (node (ref "S3") (pin "1") (pinfunction "1_1") (pintype "passive"))
      (node (ref "S3") (pin "2") (pinfunction "2_2") (pintype "passive"))
      (node (ref "SW1") (pin "P1") (pinfunction "1_P1") (pintype "passive"))
    )
    (net (code "18") (name "/AREF") (class "Default")
      (node (ref "S12") (pin "18") (pinfunction "18_18") (pintype "passive"))
    )
    (net (code "19") (name "/A_A0") (class "Default")
      (node (ref "S13") (pin "6") (pinfunction "6_6") (pintype "passive"))
      (node (ref "U$1") (pin "36") (pinfunction "PF7(ADC7)_36") (pintype "bidirectional"))
      (node (ref "U$4") (pin "A0") (pinfunction "A0_A0") (pintype "bidirectional"))
    )
    (net (code "20") (name "/A_A1") (class "Default")
      (node (ref "S13") (pin "5") (pinfunction "5_5") (pintype "passive"))
      (node (ref "U$1") (pin "37") (pinfunction "PF6(ADC6)_37") (pintype "bidirectional"))
      (node (ref "U$4") (pin "A1") (pinfunction "A1_A1") (pintype "bidirectional"))
    )
    (net (code "21") (name "/A_A2") (class "Default")
      (node (ref "S13") (pin "4") (pinfunction "4_4") (pintype "passive"))
      (node (ref "U$1") (pin "38") (pinfunction "PF5(ADC5)_38") (pintype "bidirectional"))
      (node (ref "U$4") (pin "A2") (pinfunction "A2_A2") (pintype "bidirectional"))
    )
    (net (code "22") (name "/A_A3") (class "Default")
      (node (ref "S13") (pin "3") (pinfunction "3_3") (pintype "passive"))
      (node (ref "U$1") (pin "39") (pinfunction "PF4(ADC4)_39") (pintype "bidirectional"))
      (node (ref "U$4") (pin "A3") (pinfunction "A3_A3") (pintype "bidirectional"))
    )
    (net (code "23") (name "/A_A4") (class "Default")
      (node (ref "S13") (pin "2") (pinfunction "2_2") (pintype "passive"))
      (node (ref "U$1") (pin "40") (pinfunction "PF1(ADC1)_40") (pintype "bidirectional"))
      (node (ref "U$4") (pin "A4") (pinfunction "A4/SDA_A4") (pintype "bidirectional"))
    )
    (net (code "24") (name "/A_A5") (class "Default")
      (node (ref "S13") (pin "1") (pinfunction "1_1") (pintype "passive"))
      (node (ref "U$1") (pin "41") (pinfunction "PF0(ADC0)_41") (pintype "bidirectional"))
      (node (ref "U$4") (pin "A5") (pinfunction "A5/SCL_A5") (pintype "bidirectional"))
    )
    (net (code "25") (name "/A_AREF") (class "Default")
      (node (ref "C6") (pin "1") (pinfunction "1_1") (pintype "passive"))
      (node (ref "S12") (pin "3") (pinfunction "3_3") (pintype "passive"))
      (node (ref "U$1") (pin "42") (pinfunction "AREF_42") (pintype "bidirectional"))
      (node (ref "U$4") (pin "AREF") (pinfunction "AREF_AREF") (pintype "bidirectional"))
    )
    (net (code "26") (name "/A_MISO") (class "Default")
      (node (ref "J1") (pin "1") (pinfunction "1_1") (pintype "passive"))
      (node (ref "JP5") (pin "2") (pinfunction "2_2") (pintype "passive"))
      (node (ref "M1") (pin "7") (pinfunction "MISO_7") (pintype "bidirectional"))
      (node (ref "S14") (pin "3") (pinfunction "3_3") (pintype "passive"))
      (node (ref "U$1") (pin "11") (pinfunction "PB3(MISO)_11") (pintype "bidirectional"))
    )
    (net (code "27") (name "/A_MOSI") (class "Default")
      (node (ref "J1") (pin "4") (pinfunction "4_4") (pintype "passive"))
      (node (ref "JP5") (pin "4") (pinfunction "4_4") (pintype "passive"))
      (node (ref "M1") (pin "6") (pinfunction "MOSI_6") (pintype "bidirectional"))
      (node (ref "S14") (pin "1") (pinfunction "1_1") (pintype "passive"))
      (node (ref "U$1") (pin "10") (pinfunction "PB2(MOSI)_10") (pintype "bidirectional"))
    )
    (net (code "28") (name "/A_RX") (class "Default")
      (node (ref "S11") (pin "8") (pinfunction "8_8") (pintype "passive"))
      (node (ref "U$1") (pin "20") (pinfunction "PD2(RX)_20") (pintype "bidirectional"))
      (node (ref "U$4") (pin "D0") (pinfunction "D0_D0") (pintype "bidirectional"))
    )
    (net (code "29") (name "/A_SCK") (class "Default")
      (node (ref "J1") (pin "3") (pinfunction "3_3") (pintype "passive"))
      (node (ref "JP5") (pin "3") (pinfunction "3_3") (pintype "passive"))
      (node (ref "M1") (pin "5") (pinfunction "SCK_5") (pintype "bidirectional"))
      (node (ref "S14") (pin "2") (pinfunction "2_2") (pintype "passive"))
      (node (ref "U$1") (pin "9") (pinfunction "PB1(SCK)_9") (pintype "bidirectional"))
    )
    (net (code "30") (name "/A_SCL") (class "Default")
      (node (ref "S11") (pin "5") (pinfunction "5_5") (pintype "passive"))
      (node (ref "S12") (pin "1") (pinfunction "1_1") (pintype "passive"))
      (node (ref "U$1") (pin "18") (pinfunction "PD0(SCL)_18") (pintype "bidirectional"))
      (node (ref "U$4") (pin "D3") (pinfunction "D3_D3") (pintype "bidirectional"))
      (node (ref "U$4") (pin "SCL") (pinfunction "SCL_SCL") (pintype "bidirectional"))
    )
    (net (code "31") (name "/A_SDA") (class "Default")
      (node (ref "S11") (pin "6") (pinfunction "6_6") (pintype "passive"))
      (node (ref "S12") (pin "2") (pinfunction "2_2") (pintype "passive"))
      (node (ref "U$1") (pin "19") (pinfunction "PD1(SDA)_19") (pintype "bidirectional"))
      (node (ref "U$4") (pin "D2") (pinfunction "D2_D2") (pintype "bidirectional"))
      (node (ref "U$4") (pin "SDA") (pinfunction "SDA_SDA") (pintype "bidirectional"))
    )
    (net (code "32") (name "/A_TX") (class "Default")
      (node (ref "S11") (pin "7") (pinfunction "7_7") (pintype "passive"))
      (node (ref "U$1") (pin "21") (pinfunction "PD3(TX)_21") (pintype "bidirectional"))
      (node (ref "U$4") (pin "D1") (pinfunction "D1_D1") (pintype "bidirectional"))
    )
    (net (code "33") (name "/CTS") (class "Default")
      (node (ref "U$10") (pin "12") (pinfunction "CTS_12") (pintype "output"))
    )
    (net (code "34") (name "/D+") (class "Default")
      (node (ref "R3") (pin "1") (pinfunction "1_1") (pintype "passive"))
      (node (ref "U$1") (pin "4") (pinfunction "D+_4") (pintype "bidirectional"))
    )
    (net (code "35") (name "/D-") (class "Default")
      (node (ref "R2") (pin "1") (pinfunction "1_1") (pintype "passive"))
      (node (ref "U$1") (pin "3") (pinfunction "D-_3") (pintype "bidirectional"))
    )
    (net (code "36") (name "/D4") (class "Default")
      (node (ref "S11") (pin "13") (pinfunction "13_13") (pintype "passive"))
      (node (ref "U$15") (pin "3") (pinfunction "1A_3") (pintype "bidirectional"))
    )
    (net (code "37") (name "/D5") (class "Default")
      (node (ref "R9") (pin "1") (pinfunction "1_1") (pintype "passive"))
      (node (ref "S11") (pin "14") (pinfunction "14_14") (pintype "passive"))
    )
    (net (code "38") (name "/D6") (class "Default")
      (node (ref "S11") (pin "15") (pinfunction "15_15") (pintype "passive"))
      (node (ref "SW1") (pin "A") (pinfunction "A_A") (pintype "passive"))
    )
    (net (code "39") (name "/D7") (class "Default")
      (node (ref "S11") (pin "16") (pinfunction "16_16") (pintype "passive"))
      (node (ref "SW1") (pin "B") (pinfunction "B_B") (pintype "passive"))
    )
    (net (code "40") (name "/D8") (class "Default")
      (node (ref "M1") (pin "3") (pinfunction "CE_3") (pintype "bidirectional"))
      (node (ref "R18") (pin "2") (pinfunction "2_2") (pintype "passive"))
      (node (ref "S12") (pin "11") (pinfunction "11_11") (pintype "passive"))
      (node (ref "S4") (pin "1") (pinfunction "1_1") (pintype "passive"))
      (node (ref "S4") (pin "2") (pinfunction "2_2") (pintype "passive"))
    )
    (net (code "41") (name "/D9") (class "Default")
      (node (ref "M1") (pin "4") (pinfunction "CSN_4") (pintype "bidirectional"))
      (node (ref "R19") (pin "2") (pinfunction "2_2") (pintype "passive"))
      (node (ref "S12") (pin "12") (pinfunction "12_12") (pintype "passive"))
      (node (ref "S5") (pin "1") (pinfunction "1_1") (pintype "passive"))
      (node (ref "S5") (pin "2") (pinfunction "2_2") (pintype "passive"))
    )
    (net (code "42") (name "/D10") (class "Default")
      (node (ref "R8") (pin "1") (pinfunction "1_1") (pintype "passive"))
      (node (ref "S12") (pin "13") (pinfunction "13_13") (pintype "passive"))
      (node (ref "S6") (pin "3") (pinfunction "3_3") (pintype "passive"))
    )
    (net (code "43") (name "/D11") (class "Default")
      (node (ref "R7") (pin "1") (pinfunction "1_1") (pintype "passive"))
      (node (ref "S12") (pin "14") (pinfunction "14_14") (pintype "passive"))
      (node (ref "S6") (pin "2") (pinfunction "2_2") (pintype "passive"))
    )
    (net (code "44") (name "/D12") (class "Default")
      (node (ref "R6") (pin "1") (pinfunction "1_1") (pintype "passive"))
      (node (ref "S12") (pin "15") (pinfunction "15_15") (pintype "passive"))
      (node (ref "S6") (pin "1") (pinfunction "1_1") (pintype "passive"))
    )
    (net (code "45") (name "/D13") (class "Default")
      (node (ref "IC3") (pin "5") (pinfunction "+IN_5") (pintype "input"))
      (node (ref "S12") (pin "16") (pinfunction "16_16") (pintype "passive"))
    )
    (net (code "46") (name "/DB4") (class "Default")
      (node (ref "IC4") (pin "13") (pinfunction "GP3_13") (pintype "bidirectional"))
      (node (ref "U1") (pin "11") (pinfunction "DB4_11") (pintype "bidirectional"))
    )
    (net (code "47") (name "/DB5") (class "Default")
      (node (ref "IC4") (pin "14") (pinfunction "GP4_14") (pintype "bidirectional"))
      (node (ref "U1") (pin "12") (pinfunction "DB5_12") (pintype "bidirectional"))
    )
    (net (code "48") (name "/DB6") (class "Default")
      (node (ref "IC4") (pin "15") (pinfunction "GP5_15") (pintype "bidirectional"))
      (node (ref "U1") (pin "13") (pinfunction "DB6_13") (pintype "bidirectional"))
    )
    (net (code "49") (name "/DB7") (class "Default")
      (node (ref "IC4") (pin "16") (pinfunction "GP6_16") (pintype "bidirectional"))
      (node (ref "U1") (pin "14") (pinfunction "DB7_14") (pintype "bidirectional"))
    )
    (net (code "50") (name "/DIO0") (class "Default")
      (node (ref "U$10") (pin "20") (pinfunction "DIO0_20") (pintype "bidirectional"))
    )
    (net (code "51") (name "/DIO1") (class "Default")
      (node (ref "U$10") (pin "19") (pinfunction "DIO1_19") (pintype "bidirectional"))
    )
    (net (code "52") (name "/DIO2") (class "Default")
      (node (ref "U$10") (pin "18") (pinfunction "DIO2_18") (pintype "bidirectional"))
    )
    (net (code "53") (name "/DIO3") (class "Default")
      (node (ref "U$10") (pin "17") (pinfunction "DIO3_17") (pintype "bidirectional"))
    )
    (net (code "54") (name "/DIO4") (class "Default")
      (node (ref "U$10") (pin "11") (pinfunction "DIO4_11") (pintype "bidirectional"))
    )
    (net (code "55") (name "/DIO5") (class "Default")
      (node (ref "U$10") (pin "15") (pinfunction "DIO5_15") (pintype "bidirectional"))
    )
    (net (code "56") (name "/DIO9") (class "Default")
      (node (ref "U$10") (pin "13") (pinfunction "DIO9_13") (pintype "bidirectional"))
    )
    (net (code "57") (name "/DIO11") (class "Default")
      (node (ref "U$10") (pin "7") (pinfunction "DIO11_7") (pintype "bidirectional"))
    )
    (net (code "58") (name "/DIO12") (class "Default")
      (node (ref "U$10") (pin "4") (pinfunction "DIO12_4") (pintype "bidirectional"))
    )
    (net (code "59") (name "/DTR") (class "Default")
      (node (ref "U$10") (pin "9") (pinfunction "DTR_9") (pintype "bidirectional"))
    )
    (net (code "60") (name "/E") (class "Default")
      (node (ref "IC4") (pin "12") (pinfunction "GP2_12") (pintype "bidirectional"))
      (node (ref "U1") (pin "6") (pinfunction "E_6") (pintype "input"))
    )
    (net (code "61") (name "/IOREF") (class "Default")
      (node (ref "U$4") (pin "IOREF") (pinfunction "IOREF_IOREF") (pintype "output"))
    )
    (net (code "62") (name "/LED") (class "Default")
      (node (ref "R33") (pin "2") (pinfunction "2_2") (pintype "passive"))
      (node (ref "U$15") (pin "10") (pinfunction "4Y_10") (pintype "bidirectional"))
    )
    (net (code "63") (name "/LIGHT") (class "Default")
      (node (ref "IC4") (pin "17") (pinfunction "GP7_17") (pintype "bidirectional"))
      (node (ref "R31") (pin "2") (pinfunction "2_2") (pintype "passive"))
    )
    (net (code "64") (name "/MISO") (class "Default")
      (node (ref "S14") (pin "4") (pinfunction "4_4") (pintype "passive"))
      (node (ref "U5") (pin "7") (pinfunction "DO_7") (pintype "bidirectional"))
    )
    (net (code "65") (name "/MOSI") (class "Default")
      (node (ref "S14") (pin "6") (pinfunction "6_6") (pintype "passive"))
      (node (ref "U$15") (pin "5") (pinfunction "2A_5") (pintype "bidirectional"))
    )
    (net (code "66") (name "/RES") (class "Default")
      (node (ref "U$10") (pin "8") (pinfunction "RES_8") (pintype "bidirectional"))
    )
    (net (code "67") (name "/RES1") (class "Default")
      (node (ref "U$10") (pin "14") (pinfunction "RES_14") (pintype "bidirectional"))
    )
    (net (code "68") (name "/RESET") (class "Default")
      (node (ref "U$10") (pin "5") (pinfunction "RESET_5") (pintype "input"))
    )
    (net (code "69") (name "/RS") (class "Default")
      (node (ref "IC4") (pin "11") (pinfunction "GP1_11") (pintype "bidirectional"))
      (node (ref "U1") (pin "4") (pinfunction "RS_4") (pintype "input"))
    )
    (net (code "70") (name "/RSSI") (class "Default")
      (node (ref "R41") (pin "2") (pinfunction "2_2") (pintype "passive"))
      (node (ref "U$10") (pin "6") (pinfunction "RSSI_6") (pintype "bidirectional"))
    )
    (net (code "71") (name "/RTS") (class "Default")
      (node (ref "U$10") (pin "16") (pinfunction "RTS_16") (pintype "input"))
    )
    (net (code "72") (name "/RX") (class "Default")
      (node (ref "BLUETOOTH") (pin "3") (pinfunction "3_3") (pintype "passive"))
      (node (ref "Q3") (pin "3") (pinfunction "D_3") (pintype "passive"))
      (node (ref "R38") (pin "1") (pinfunction "1_1") (pintype "passive"))
      (node (ref "S11") (pin "9") (pinfunction "9_9") (pintype "passive"))
    )
    (net (code "73") (name "/RXLED") (class "Default")
      (node (ref "LED2") (pin "C") (pinfunction "C_C") (pintype "passive"))
      (node (ref "U$1") (pin "8") (pinfunction "PB0(SS)_8") (pintype "bidirectional"))
    )
    (net (code "74") (name "/SCK") (class "Default")
      (node (ref "S14") (pin "5") (pinfunction "5_5") (pintype "passive"))
      (node (ref "U$15") (pin "7") (pinfunction "3A_7") (pintype "bidirectional"))
      (node (ref "U$15") (pin "9") (pinfunction "4A_9") (pintype "bidirectional"))
    )
    (net (code "75") (name "/SCL") (class "Default")
      (node (ref "IC4") (pin "1") (pinfunction "SCL_1") (pintype "bidirectional"))
      (node (ref "R35") (pin "1") (pinfunction "1_1") (pintype "passive"))
      (node (ref "S11") (pin "12") (pinfunction "12_12") (pintype "passive"))
      (node (ref "S12") (pin "20") (pinfunction "20_20") (pintype "passive"))
      (node (ref "U$7") (pin "6") (pinfunction "SCL_6") (pintype "bidirectional"))
      (node (ref "U2") (pin "6") (pinfunction "SCL_6") (pintype "bidirectional"))
    )
    (net (code "76") (name "/SDA") (class "Default")
      (node (ref "IC4") (pin "2") (pinfunction "SDA_2") (pintype "bidirectional"))
      (node (ref "R32") (pin "1") (pinfunction "1_1") (pintype "passive"))
      (node (ref "S11") (pin "11") (pinfunction "11_11") (pintype "passive"))
      (node (ref "S12") (pin "19") (pinfunction "19_19") (pintype "passive"))
      (node (ref "U$7") (pin "5") (pinfunction "SDA_5") (pintype "bidirectional"))
      (node (ref "U2") (pin "5") (pinfunction "SDA_5") (pintype "bidirectional"))
    )
    (net (code "77") (name "/SQW") (class "Default")
      (node (ref "U$7") (pin "7") (pinfunction "SQW_7") (pintype "bidirectional"))
    )
    (net (code "78") (name "/S_D10") (class "Default")
      (node (ref "IC6") (pin "1") (pinfunction "DIN_1") (pintype "input"))
      (node (ref "S6") (pin "4") (pinfunction "4_4") (pintype "passive"))
    )
    (net (code "79") (name "/S_D11") (class "Default")
      (node (ref "IC6") (pin "12") (pinfunction "LOAD_12") (pintype "input"))
      (node (ref "S6") (pin "5") (pinfunction "5_5") (pintype "passive"))
    )
    (net (code "80") (name "/S_D12") (class "Default")
      (node (ref "IC6") (pin "13") (pinfunction "CLK_13") (pintype "input"))
      (node (ref "S6") (pin "6") (pinfunction "6_6") (pintype "passive"))
    )
    (net (code "81") (name "/TX") (class "Default")
      (node (ref "BLUETOOTH") (pin "4") (pinfunction "4_4") (pintype "passive"))
      (node (ref "Q4") (pin "3") (pinfunction "D_3") (pintype "passive"))
      (node (ref "R40") (pin "1") (pinfunction "1_1") (pintype "passive"))
      (node (ref "S11") (pin "10") (pinfunction "10_10") (pintype "passive"))
    )
    (net (code "82") (name "/TXLED") (class "Default")
      (node (ref "LED8") (pin "C") (pinfunction "C_C") (pintype "passive"))
      (node (ref "U$1") (pin "22") (pinfunction "PD5_22") (pintype "bidirectional"))
    )
    (net (code "83") (name "/VUSB") (class "Default")
      (node (ref "C19") (pin "1") (pinfunction "1_1") (pintype "passive"))
      (node (ref "C20") (pin "A") (pinfunction "+_A") (pintype "passive"))
      (node (ref "L1") (pin "2") (pinfunction "2_2") (pintype "passive"))
      (node (ref "Q2") (pin "1") (pinfunction "D_1") (pintype "passive"))
      (node (ref "U$1") (pin "7") (pinfunction "VBUS_7") (pintype "bidirectional"))
    )
    (net (code "84") (name "/~{RESET}") (class "Default")
      (node (ref "J1") (pin "5") (pinfunction "5_5") (pintype "passive"))
      (node (ref "JP5") (pin "5") (pinfunction "5_5") (pintype "passive"))
      (node (ref "R48") (pin "1") (pinfunction "1_1") (pintype "passive"))
      (node (ref "S1") (pin "1") (pinfunction "1_1") (pintype "passive"))
      (node (ref "S1") (pin "2") (pinfunction "2_2") (pintype "passive"))
      (node (ref "U$1") (pin "13") (pinfunction "~{RESET}_13") (pintype "bidirectional"))
      (node (ref "U$4") (pin "RESET") (pinfunction "/RESET_RESET") (pintype "bidirectional"))
    )
    (net (code "85") (name "3.3V") (class "Default")
      (node (ref "C11") (pin "1") (pinfunction "1_1") (pintype "passive"))
      (node (ref "C12") (pin "A") (pinfunction "+_A") (pintype "passive"))
      (node (ref "C17") (pin "1") (pinfunction "1_1") (pintype "passive"))
      (node (ref "C27") (pin "1") (pinfunction "1_1") (pintype "passive"))
      (node (ref "IC3") (pin "2") (pinfunction "-IN_2") (pintype "input"))
      (node (ref "IC5") (pin "4") (pinfunction "OUT_4") (pintype "passive"))
      (node (ref "JP8") (pin "2") (pinfunction "2_2") (pintype "passive"))
      (node (ref "JP8") (pin "3") (pinfunction "3_3") (pintype "passive"))
      (node (ref "JP8") (pin "5") (pinfunction "5_5") (pintype "passive"))
      (node (ref "JP8") (pin "6") (pinfunction "6_6") (pintype "passive"))
      (node (ref "Q3") (pin "1") (pinfunction "G_1") (pintype "passive"))
      (node (ref "Q4") (pin "1") (pinfunction "G_1") (pintype "passive"))
      (node (ref "R37") (pin "2") (pinfunction "2_2") (pintype "passive"))
      (node (ref "R39") (pin "2") (pinfunction "2_2") (pintype "passive"))
      (node (ref "R42") (pin "2") (pinfunction "2_2") (pintype "passive"))
      (node (ref "R43") (pin "2") (pinfunction "2_2") (pintype "passive"))
      (node (ref "U$10") (pin "1") (pinfunction "VDD_1") (pintype "power_in"))
      (node (ref "U$15") (pin "1") (pinfunction "VCC_1") (pintype "bidirectional"))
      (node (ref "U$4") (pin "3V") (pinfunction "3V_3V") (pintype "power_in"))
      (node (ref "U5") (pin "4") (pinfunction "VCC_4") (pintype "bidirectional"))
    )
    (net (code "86") (name "DIN") (class "Default")
      (node (ref "JP8") (pin "1") (pinfunction "1_1") (pintype "passive"))
      (node (ref "LED12") (pin "C") (pinfunction "C_C") (pintype "passive"))
      (node (ref "Q4") (pin "2") (pinfunction "S_2") (pintype "passive"))
      (node (ref "R39") (pin "1") (pinfunction "1_1") (pintype "passive"))
      (node (ref "U$10") (pin "3") (pinfunction "DIN_3") (pintype "input"))
    )
    (net (code "87") (name "DOUT") (class "Default")
      (node (ref "JP8") (pin "8") (pinfunction "8_8") (pintype "passive"))
      (node (ref "LED11") (pin "C") (pinfunction "C_C") (pintype "passive"))
      (node (ref "Q3") (pin "2") (pinfunction "S_2") (pintype "passive"))
      (node (ref "R37") (pin "1") (pinfunction "1_1") (pintype "passive"))
      (node (ref "U$10") (pin "2") (pinfunction "DOUT_2") (pintype "output"))
    )
    (net (code "88") (name "GND") (class "Default")
      (node (ref "BLUETOOTH") (pin "2") (pinfunction "2_2") (pintype "passive"))
      (node (ref "C1") (pin "1") (pinfunction "1_1") (pintype "passive"))
      (node (ref "C10") (pin "C") (pinfunction "-_C") (pintype "passive"))
      (node (ref "C11") (pin "2") (pinfunction "2_2") (pintype "passive"))
      (node (ref "C12") (pin "C") (pinfunction "-_C") (pintype "passive"))
      (node (ref "C13") (pin "2") (pinfunction "2_2") (pintype "passive"))
      (node (ref "C14") (pin "C") (pinfunction "-_C") (pintype "passive"))
      (node (ref "C15") (pin "2") (pinfunction "2_2") (pintype "passive"))
      (node (ref "C16") (pin "2") (pinfunction "2_2") (pintype "passive"))
      (node (ref "C17") (pin "2") (pinfunction "2_2") (pintype "passive"))
      (node (ref "C18") (pin "2") (pinfunction "2_2") (pintype "passive"))
      (node (ref "C19") (pin "2") (pinfunction "2_2") (pintype "passive"))
      (node (ref "C2") (pin "1") (pinfunction "1_1") (pintype "passive"))
      (node (ref "C20") (pin "C") (pinfunction "-_C") (pintype "passive"))
      (node (ref "C21") (pin "2") (pinfunction "2_2") (pintype "passive"))
      (node (ref "C22") (pin "2") (pinfunction "2_2") (pintype "passive"))
      (node (ref "C23") (pin "2") (pinfunction "2_2") (pintype "passive"))
      (node (ref "C24") (pin "2") (pinfunction "2_2") (pintype "passive"))
      (node (ref "C25") (pin "2") (pinfunction "2_2") (pintype "passive"))
      (node (ref "C26") (pin "2") (pinfunction "2_2") (pintype "passive"))
      (node (ref "C27") (pin "2") (pinfunction "2_2") (pintype "passive"))
      (node (ref "C28") (pin "-") (pinfunction "-_-") (pintype "passive"))
      (node (ref "C3") (pin "1") (pinfunction "1_1") (pintype "passive"))
      (node (ref "C30") (pin "-") (pinfunction "-_-") (pintype "passive"))
      (node (ref "C4") (pin "1") (pinfunction "1_1") (pintype "passive"))
      (node (ref "C5") (pin "1") (pinfunction "1_1") (pintype "passive"))
      (node (ref "C6") (pin "2") (pinfunction "2_2") (pintype "passive"))
      (node (ref "D1") (pin "A") (pinfunction "A_A") (pintype "passive"))
      (node (ref "IC1") (pin "3") (pinfunction "GND_3") (pintype "power_in"))
      (node (ref "IC1") (pin "5") (pinfunction "OFF_5") (pintype "input"))
      (node (ref "IC1") (pin "GND") (pinfunction "TAB_GND") (pintype "bidirectional"))
      (node (ref "IC2") (pin "3") (pinfunction "GND_3") (pintype "power_in"))
      (node (ref "IC3") (pin "4") (pinfunction "V-_4") (pintype "power_in"))
      (node (ref "IC4") (pin "9") (pinfunction "GND_9") (pintype "power_in"))
      (node (ref "IC5") (pin "1") (pinfunction "ADJ_1") (pintype "input"))
      (node (ref "IC6") (pin "4") (pinfunction "GND_4") (pintype "power_in"))
      (node (ref "IC6") (pin "9") (pinfunction "GND_9") (pintype "power_in"))
      (node (ref "J1") (pin "6") (pinfunction "6_6") (pintype "passive"))
      (node (ref "J2") (pin "GND") (pinfunction "GND_GND") (pintype "bidirectional"))
      (node (ref "J2") (pin "GNDBREAK") (pinfunction "GNDBREAK_GNDBREAK") (pintype "bidirectional"))
      (node (ref "JP5") (pin "6") (pinfunction "6_6") (pintype "passive"))
      (node (ref "JP8") (pin "7") (pinfunction "7_7") (pintype "passive"))
      (node (ref "LED10") (pin "C") (pinfunction "C_C") (pintype "passive"))
      (node (ref "LED3") (pin "K") (pinfunction "C_K") (pintype "passive"))
      (node (ref "LED4") (pin "K") (pinfunction "C_K") (pintype "passive"))
      (node (ref "LED5") (pin "K") (pinfunction "C_K") (pintype "passive"))
      (node (ref "LED6") (pin "K") (pinfunction "C_K") (pintype "passive"))
      (node (ref "LED7") (pin "C") (pinfunction "C_C") (pintype "passive"))
      (node (ref "M1") (pin "1") (pinfunction "GND_1") (pintype "power_in"))
      (node (ref "P1") (pin "A") (pinfunction "A_A") (pintype "passive"))
      (node (ref "Q1") (pin "1") (pinfunction "G_1") (pintype "passive"))
      (node (ref "R10") (pin "2") (pinfunction "2_2") (pintype "passive"))
      (node (ref "R20") (pin "1") (pinfunction "1_1") (pintype "passive"))
      (node (ref "R22") (pin "1") (pinfunction "1_1") (pintype "passive"))
      (node (ref "R23") (pin "2") (pinfunction "P$2_2") (pintype "bidirectional"))
      (node (ref "R26") (pin "1") (pinfunction "1_1") (pintype "passive"))
      (node (ref "R28") (pin "2") (pinfunction "2_2") (pintype "passive"))
      (node (ref "R29") (pin "2") (pinfunction "2_2") (pintype "passive"))
      (node (ref "R30") (pin "2") (pinfunction "2_2") (pintype "passive"))
      (node (ref "R34") (pin "2") (pinfunction "2_2") (pintype "passive"))
      (node (ref "R44") (pin "2") (pinfunction "2_2") (pintype "passive"))
      (node (ref "R47") (pin "1") (pinfunction "1_1") (pintype "passive"))
      (node (ref "R5") (pin "2") (pinfunction "2_2") (pintype "passive"))
      (node (ref "S1") (pin "3") (pinfunction "3_3") (pintype "passive"))
      (node (ref "S1") (pin "4") (pinfunction "4_4") (pintype "passive"))
      (node (ref "S12") (pin "17") (pinfunction "17_17") (pintype "passive"))
      (node (ref "S12") (pin "4") (pinfunction "4_4") (pintype "passive"))
      (node (ref "S4") (pin "3") (pinfunction "3_3") (pintype "passive"))
      (node (ref "S4") (pin "4") (pinfunction "4_4") (pintype "passive"))
      (node (ref "S5") (pin "3") (pinfunction "3_3") (pintype "passive"))
      (node (ref "S5") (pin "4") (pinfunction "4_4") (pintype "passive"))
      (node (ref "SW1") (pin "C") (pinfunction "C_C") (pintype "passive"))
      (node (ref "T1") (pin "E") (pinfunction "E_E") (pintype "passive"))
      (node (ref "T2") (pin "E") (pinfunction "E_E") (pintype "passive"))
      (node (ref "T3") (pin "E") (pinfunction "E_E") (pintype "passive"))
      (node (ref "T4") (pin "E") (pinfunction "E_E") (pintype "passive"))
      (node (ref "U$1") (pin "15") (pinfunction "GND_15") (pintype "bidirectional"))
      (node (ref "U$1") (pin "23") (pinfunction "GND_23") (pintype "bidirectional"))
      (node (ref "U$1") (pin "35") (pinfunction "GND_35") (pintype "bidirectional"))
      (node (ref "U$1") (pin "43") (pinfunction "GND_43") (pintype "bidirectional"))
      (node (ref "U$1") (pin "5") (pinfunction "UGND_5") (pintype "bidirectional"))
      (node (ref "U$10") (pin "10") (pinfunction "GND_10") (pintype "power_in"))
      (node (ref "U$15") (pin "11") (pinfunction "5A_11") (pintype "bidirectional"))
      (node (ref "U$15") (pin "14") (pinfunction "6A_14") (pintype "bidirectional"))
      (node (ref "U$15") (pin "8") (pinfunction "GND_8") (pintype "bidirectional"))
      (node (ref "U$3") (pin "GND") (pinfunction "GND_GND") (pintype "bidirectional"))
      (node (ref "U$3") (pin "S1") (pinfunction "P$1_S1") (pintype "bidirectional"))
      (node (ref "U$3") (pin "S2") (pinfunction "P$2_S2") (pintype "bidirectional"))
      (node (ref "U$4") (pin "GND") (pinfunction "GND_GND") (pintype "power_in"))
      (node (ref "U$4") (pin "GND1") (pinfunction "GND1_GND1") (pintype "power_in"))
      (node (ref "U$4") (pin "GND2") (pinfunction "GND2_GND2") (pintype "power_in"))
      (node (ref "U$5") (pin "1") (pinfunction "A_1") (pintype "passive"))
      (node (ref "U$6") (pin "-") (pinfunction "-_-") (pintype "passive"))
      (node (ref "U$7") (pin "4") (pinfunction "GND_4") (pintype "bidirectional"))
      (node (ref "U$9") (pin "P$1") (pinfunction "3_P$1") (pintype "passive"))
      (node (ref "U1") (pin "1") (pinfunction "VSS_1") (pintype "power_in"))
      (node (ref "U1") (pin "5") (pinfunction "R/W_5") (pintype "input"))
      (node (ref "U2") (pin "1") (pinfunction "A0_1") (pintype "bidirectional"))
      (node (ref "U2") (pin "2") (pinfunction "A1_2") (pintype "bidirectional"))
      (node (ref "U2") (pin "3") (pinfunction "A2_3") (pintype "bidirectional"))
      (node (ref "U2") (pin "4") (pinfunction "VSS_4") (pintype "power_in"))
      (node (ref "U2") (pin "7") (pinfunction "WP_7") (pintype "bidirectional"))
      (node (ref "U5") (pin "6") (pinfunction "GND_6") (pintype "bidirectional"))
      (node (ref "U5") (pin "CD1") (pinfunction "SHIELD_CD1") (pintype "bidirectional"))
      (node (ref "U5") (pin "CD2") (pinfunction "SHIELD_CD2") (pintype "bidirectional"))
      (node (ref "U5") (pin "GND1") (pinfunction "SHIELD_GND1") (pintype "bidirectional"))
      (node (ref "U5") (pin "GND3") (pinfunction "SHIELD_GND3") (pintype "bidirectional"))
    )
    (net (code "89") (name "Net-(D2-PadA)") (class "Default")
      (node (ref "D2") (pin "A") (pinfunction "A_A") (pintype "passive"))
      (node (ref "K4") (pin "2") (pinfunction "2_2") (pintype "passive"))
      (node (ref "LED1") (pin "C") (pinfunction "C_C") (pintype "passive"))
      (node (ref "T3") (pin "C") (pinfunction "C_C") (pintype "passive"))
    )
    (net (code "90") (name "Net-(IC1-OUT)") (class "Default")
      (node (ref "D1") (pin "C") (pinfunction "C_C") (pintype "passive"))
      (node (ref "IC1") (pin "2") (pinfunction "OUT_2") (pintype "output"))
      (node (ref "L2") (pin "1") (pinfunction "1_1") (pintype "passive"))
    )
    (net (code "91") (name "Net-(IC3A-+IN)") (class "Default")
      (node (ref "C18") (pin "1") (pinfunction "1_1") (pintype "passive"))
      (node (ref "IC3") (pin "3") (pinfunction "+IN_3") (pintype "input"))
      (node (ref "R34") (pin "1") (pinfunction "1_1") (pintype "passive"))
      (node (ref "R36") (pin "2") (pinfunction "2_2") (pintype "passive"))
    )
    (net (code "92") (name "Net-(IC3A-OUT)") (class "Default")
      (node (ref "IC3") (pin "1") (pinfunction "OUT_1") (pintype "output"))
      (node (ref "Q2") (pin "3") (pinfunction "G_3") (pintype "passive"))
    )
    (net (code "93") (name "Net-(IC3B--IN)") (class "Default")
      (node (ref "IC3") (pin "6") (pinfunction "-IN_6") (pintype "input"))
      (node (ref "IC3") (pin "7") (pinfunction "OUT_7") (pintype "output"))
      (node (ref "R1") (pin "1") (pinfunction "1_1") (pintype "passive"))
    )
    (net (code "94") (name "Net-(IC4-A0)") (class "Default")
      (node (ref "IC4") (pin "5") (pinfunction "A0_5") (pintype "input"))
      (node (ref "R28") (pin "1") (pinfunction "1_1") (pintype "passive"))
    )
    (net (code "95") (name "Net-(IC4-A1)") (class "Default")
      (node (ref "IC4") (pin "4") (pinfunction "A1_4") (pintype "input"))
      (node (ref "R29") (pin "1") (pinfunction "1_1") (pintype "passive"))
    )
    (net (code "96") (name "Net-(IC4-A2)") (class "Default")
      (node (ref "IC4") (pin "3") (pinfunction "A2_3") (pintype "input"))
      (node (ref "R30") (pin "1") (pinfunction "1_1") (pintype "passive"))
    )
    (net (code "97") (name "Net-(IC4-{slash}RST)") (class "Default")
      (node (ref "IC4") (pin "6") (pinfunction "/RST_6") (pintype "input"))
      (node (ref "R45") (pin "1") (pinfunction "1_1") (pintype "passive"))
    )
    (net (code "98") (name "Net-(IC6-DIG0)") (class "Default")
      (node (ref "IC6") (pin "2") (pinfunction "DIG0_2") (pintype "output"))
      (node (ref "U$13") (pin "12") (pinfunction "DIG1_12") (pintype "input"))
    )
    (net (code "99") (name "Net-(IC6-DIG1)") (class "Default")
      (node (ref "IC6") (pin "11") (pinfunction "DIG1_11") (pintype "output"))
      (node (ref "U$13") (pin "9") (pinfunction "DIG2_9") (pintype "input"))
    )
    (net (code "100") (name "Net-(IC6-DIG2)") (class "Default")
      (node (ref "IC6") (pin "6") (pinfunction "DIG2_6") (pintype "output"))
      (node (ref "U$13") (pin "8") (pinfunction "DIG3_8") (pintype "input"))
    )
    (net (code "101") (name "Net-(IC6-DIG3)") (class "Default")
      (node (ref "IC6") (pin "7") (pinfunction "DIG3_7") (pintype "output"))
      (node (ref "U$13") (pin "6") (pinfunction "DIG4_6") (pintype "input"))
    )
    (net (code "102") (name "Net-(IC6-ISET)") (class "Default")
      (node (ref "IC6") (pin "18") (pinfunction "ISET_18") (pintype "input"))
      (node (ref "R46") (pin "1") (pinfunction "1_1") (pintype "passive"))
    )
    (net (code "103") (name "Net-(IC6-SEGA)") (class "Default")
      (node (ref "IC6") (pin "14") (pinfunction "SEGA_14") (pintype "output"))
      (node (ref "U$13") (pin "11") (pinfunction "A_11") (pintype "input"))
    )
    (net (code "104") (name "Net-(IC6-SEGB)") (class "Default")
      (node (ref "IC6") (pin "16") (pinfunction "SEGB_16") (pintype "output"))
      (node (ref "U$13") (pin "7") (pinfunction "B_7") (pintype "input"))
    )
    (net (code "105") (name "Net-(IC6-SEGC)") (class "Default")
      (node (ref "IC6") (pin "20") (pinfunction "SEGC_20") (pintype "output"))
      (node (ref "U$13") (pin "4") (pinfunction "C_4") (pintype "input"))
    )
    (net (code "106") (name "Net-(IC6-SEGD)") (class "Default")
      (node (ref "IC6") (pin "23") (pinfunction "SEGD_23") (pintype "output"))
      (node (ref "U$13") (pin "2") (pinfunction "D_2") (pintype "input"))
    )
    (net (code "107") (name "Net-(IC6-SEGDP)") (class "Default")
      (node (ref "IC6") (pin "22") (pinfunction "SEGDP_22") (pintype "output"))
      (node (ref "U$13") (pin "3") (pinfunction "DP_3") (pintype "input"))
    )
    (net (code "108") (name "Net-(IC6-SEGE)") (class "Default")
      (node (ref "IC6") (pin "21") (pinfunction "SEGE_21") (pintype "output"))
      (node (ref "U$13") (pin "1") (pinfunction "E_1") (pintype "input"))
    )
    (net (code "109") (name "Net-(IC6-SEGF)") (class "Default")
      (node (ref "IC6") (pin "15") (pinfunction "SEGF_15") (pintype "output"))
      (node (ref "U$13") (pin "10") (pinfunction "F_10") (pintype "input"))
    )
    (net (code "110") (name "Net-(IC6-SEGG)") (class "Default")
      (node (ref "IC6") (pin "17") (pinfunction "SEGG_17") (pintype "output"))
      (node (ref "U$13") (pin "5") (pinfunction "G_5") (pintype "input"))
    )
    (net (code "111") (name "Net-(JP1-Pad1)") (class "Default")
      (node (ref "JP1") (pin "1") (pinfunction "1_1") (pintype "passive"))
      (node (ref "K4") (pin "S") (pinfunction "S_S") (pintype "passive"))
    )
    (net (code "112") (name "Net-(JP1-Pad2)") (class "Default")
      (node (ref "JP1") (pin "2") (pinfunction "2_2") (pintype "passive"))
      (node (ref "K4") (pin "P") (pinfunction "P_P") (pintype "passive"))
    )
    (net (code "113") (name "Net-(JP1-Pad3)") (class "Default")
      (node (ref "JP1") (pin "3") (pinfunction "3_3") (pintype "passive"))
      (node (ref "K4") (pin "O") (pinfunction "O_O") (pintype "passive"))
    )
    (net (code "114") (name "Net-(L1-Pad1)") (class "Default")
      (node (ref "L1") (pin "1") (pinfunction "1_1") (pintype "passive"))
      (node (ref "U$3") (pin "VBUS") (pinfunction "VBUS_VBUS") (pintype "bidirectional"))
    )
    (net (code "115") (name "Net-(LED1-PadA)") (class "Default")
      (node (ref "LED1") (pin "A") (pinfunction "A_A") (pintype "passive"))
      (node (ref "R15") (pin "1") (pinfunction "1_1") (pintype "passive"))
    )
    (net (code "116") (name "Net-(LED2-PadA)") (class "Default")
      (node (ref "LED2") (pin "A") (pinfunction "A_A") (pintype "passive"))
      (node (ref "R14") (pin "1") (pinfunction "1_1") (pintype "passive"))
    )
    (net (code "117") (name "Net-(LED3-PadA)") (class "Default")
      (node (ref "LED3") (pin "A") (pinfunction "A_A") (pintype "passive"))
      (node (ref "R1") (pin "2") (pinfunction "2_2") (pintype "passive"))
    )
    (net (code "118") (name "Net-(LED4-PadA)") (class "Default")
      (node (ref "LED4") (pin "A") (pinfunction "A_A") (pintype "passive"))
      (node (ref "R6") (pin "2") (pinfunction "2_2") (pintype "passive"))
    )
    (net (code "119") (name "Net-(LED5-PadA)") (class "Default")
      (node (ref "LED5") (pin "A") (pinfunction "A_A") (pintype "passive"))
      (node (ref "R7") (pin "2") (pinfunction "2_2") (pintype "passive"))
    )
    (net (code "120") (name "Net-(LED6-PadA)") (class "Default")
      (node (ref "LED6") (pin "A") (pinfunction "A_A") (pintype "passive"))
      (node (ref "R8") (pin "2") (pinfunction "2_2") (pintype "passive"))
    )
    (net (code "121") (name "Net-(LED7-PadA)") (class "Default")
      (node (ref "LED7") (pin "A") (pinfunction "A_A") (pintype "passive"))
      (node (ref "R16") (pin "1") (pinfunction "1_1") (pintype "passive"))
    )
    (net (code "122") (name "Net-(LED8-PadA)") (class "Default")
      (node (ref "LED8") (pin "A") (pinfunction "A_A") (pintype "passive"))
      (node (ref "R17") (pin "1") (pinfunction "1_1") (pintype "passive"))
    )
    (net (code "123") (name "Net-(LED9-PadA)") (class "Default")
      (node (ref "LED9") (pin "A") (pinfunction "A_A") (pintype "passive"))
      (node (ref "R33") (pin "1") (pinfunction "1_1") (pintype "passive"))
    )
    (net (code "124") (name "Net-(LED10-PadA)") (class "Default")
      (node (ref "LED10") (pin "A") (pinfunction "A_A") (pintype "passive"))
      (node (ref "R41") (pin "1") (pinfunction "1_1") (pintype "passive"))
    )
    (net (code "125") (name "Net-(LED11-PadA)") (class "Default")
      (node (ref "LED11") (pin "A") (pinfunction "A_A") (pintype "passive"))
      (node (ref "R42") (pin "1") (pinfunction "1_1") (pintype "passive"))
    )
    (net (code "126") (name "Net-(LED12-PadA)") (class "Default")
      (node (ref "LED12") (pin "A") (pinfunction "A_A") (pintype "passive"))
      (node (ref "R43") (pin "1") (pinfunction "1_1") (pintype "passive"))
    )
    (net (code "127") (name "Net-(LED13-PadA)") (class "Default")
      (node (ref "LED13") (pin "A") (pinfunction "A_A") (pintype "passive"))
      (node (ref "R47") (pin "2") (pinfunction "2_2") (pintype "passive"))
    )
    (net (code "128") (name "Net-(MOTOR-Pad2)") (class "Default")
      (node (ref "MOTOR") (pin "2") (pinfunction "2_2") (pintype "passive"))
      (node (ref "T1") (pin "C") (pinfunction "C_C") (pintype "passive"))
    )
    (net (code "129") (name "Net-(Q1-D)") (class "Default")
      (node (ref "LED13") (pin "C") (pinfunction "C_C") (pintype "passive"))
      (node (ref "Q1") (pin "3") (pinfunction "D_3") (pintype "passive"))
      (node (ref "S9") (pin "3") (pinfunction "S_3") (pintype "passive"))
    )
    (net (code "130") (name "Net-(R2-Pad2)") (class "Default")
      (node (ref "R2") (pin "2") (pinfunction "2_2") (pintype "passive"))
      (node (ref "U$3") (pin "D-") (pinfunction "D-_D-") (pintype "bidirectional"))
    )
    (net (code "131") (name "Net-(R3-Pad2)") (class "Default")
      (node (ref "R3") (pin "2") (pinfunction "2_2") (pintype "passive"))
      (node (ref "U$3") (pin "D+") (pinfunction "D+_D+") (pintype "bidirectional"))
    )
    (net (code "132") (name "Net-(R11-Pad1)") (class "Default")
      (node (ref "R11") (pin "1") (pinfunction "1_1") (pintype "passive"))
      (node (ref "S2") (pin "3") (pinfunction "3_3") (pintype "passive"))
      (node (ref "S2") (pin "4") (pinfunction "4_4") (pintype "passive"))
    )
    (net (code "133") (name "Net-(R12-Pad1)") (class "Default")
      (node (ref "R12") (pin "1") (pinfunction "1_1") (pintype "passive"))
      (node (ref "S3") (pin "3") (pinfunction "3_3") (pintype "passive"))
      (node (ref "S3") (pin "4") (pinfunction "4_4") (pintype "passive"))
    )
    (net (code "134") (name "Net-(R20-Pad2)") (class "Default")
      (node (ref "R20") (pin "2") (pinfunction "2_2") (pintype "passive"))
      (node (ref "R9") (pin "2") (pinfunction "2_2") (pintype "passive"))
      (node (ref "T1") (pin "B") (pinfunction "B_B") (pintype "passive"))
    )
    (net (code "135") (name "Net-(R21-Pad2)") (class "Default")
      (node (ref "R21") (pin "2") (pinfunction "2_2") (pintype "passive"))
      (node (ref "R22") (pin "2") (pinfunction "2_2") (pintype "passive"))
      (node (ref "T2") (pin "B") (pinfunction "B_B") (pintype "passive"))
    )
    (net (code "136") (name "Net-(R25-Pad2)") (class "Default")
      (node (ref "R25") (pin "2") (pinfunction "2_2") (pintype "passive"))
      (node (ref "R26") (pin "2") (pinfunction "2_2") (pintype "passive"))
      (node (ref "T3") (pin "B") (pinfunction "B_B") (pintype "passive"))
    )
    (net (code "137") (name "Net-(R31-Pad1)") (class "Default")
      (node (ref "R31") (pin "1") (pinfunction "1_1") (pintype "passive"))
      (node (ref "R44") (pin "1") (pinfunction "1_1") (pintype "passive"))
      (node (ref "T4") (pin "B") (pinfunction "B_B") (pintype "passive"))
    )
    (net (code "138") (name "Net-(S9-P)") (class "Default")
      (node (ref "J2") (pin "PWR") (pinfunction "PWR_PWR") (pintype "bidirectional"))
      (node (ref "S9") (pin "2") (pinfunction "P_2") (pintype "passive"))
    )
    (net (code "139") (name "Net-(SG2-Pad-)") (class "Default")
      (node (ref "SG2") (pin "-") (pinfunction "-_-") (pintype "passive"))
      (node (ref "T2") (pin "C") (pinfunction "C_C") (pintype "passive"))
    )
    (net (code "140") (name "Net-(SW1B-2)") (class "Default")
      (node (ref "R27") (pin "2") (pinfunction "2_2") (pintype "passive"))
      (node (ref "SW1") (pin "P2") (pinfunction "2_P2") (pintype "passive"))
    )
    (net (code "141") (name "Net-(U$1-PE2{slash}~{HWB})") (class "Default")
      (node (ref "R5") (pin "1") (pinfunction "1_1") (pintype "passive"))
      (node (ref "U$1") (pin "33") (pinfunction "PE2/~{HWB}_33") (pintype "bidirectional"))
    )
    (net (code "142") (name "Net-(U$1-UCAP)") (class "Default")
      (node (ref "C1") (pin "2") (pinfunction "2_2") (pintype "passive"))
      (node (ref "U$1") (pin "6") (pinfunction "UCAP_6") (pintype "bidirectional"))
    )
    (net (code "143") (name "Net-(U$1-XTAL1)") (class "Default")
      (node (ref "C2") (pin "2") (pinfunction "2_2") (pintype "passive"))
      (node (ref "R4") (pin "2") (pinfunction "2_2") (pintype "passive"))
      (node (ref "U$1") (pin "17") (pinfunction "XTAL1_17") (pintype "bidirectional"))
      (node (ref "Y1") (pin "3") (pinfunction "2_3") (pintype "passive"))
    )
    (net (code "144") (name "Net-(U$1-XTAL2)") (class "Default")
      (node (ref "C3") (pin "2") (pinfunction "2_2") (pintype "passive"))
      (node (ref "R4") (pin "1") (pinfunction "1_1") (pintype "passive"))
      (node (ref "U$1") (pin "16") (pinfunction "XTAL2_16") (pintype "bidirectional"))
      (node (ref "Y1") (pin "1") (pinfunction "1_1") (pintype "passive"))
    )
    (net (code "145") (name "Net-(U$5-S)") (class "Default")
      (node (ref "U$5") (pin "2") (pinfunction "S_2") (pintype "passive"))
      (node (ref "U1") (pin "3") (pinfunction "VO_3") (pintype "bidirectional"))
    )
    (net (code "146") (name "Net-(U$6-+)") (class "Default")
      (node (ref "U$6") (pin "+$1") (pinfunction "+_+$1") (pintype "passive"))
      (node (ref "U$7") (pin "3") (pinfunction "VBATT_3") (pintype "bidirectional"))
    )
    (net (code "147") (name "Net-(U$7-X1)") (class "Default")
      (node (ref "U$7") (pin "1") (pinfunction "X1_1") (pintype "bidirectional"))
      (node (ref "U$9") (pin "2") (pinfunction "2_2") (pintype "passive"))
    )
    (net (code "148") (name "Net-(U$7-X2)") (class "Default")
      (node (ref "U$7") (pin "2") (pinfunction "X2_2") (pintype "bidirectional"))
      (node (ref "U$9") (pin "1") (pinfunction "1_1") (pintype "passive"))
    )
    (net (code "149") (name "Net-(U$15-1Y)") (class "Default")
      (node (ref "LED9") (pin "C") (pinfunction "C_C") (pintype "passive"))
      (node (ref "U$15") (pin "2") (pinfunction "1Y_2") (pintype "bidirectional"))
      (node (ref "U5") (pin "2") (pinfunction "CS_2") (pintype "bidirectional"))
    )
    (net (code "150") (name "Net-(U$15-2Y)") (class "Default")
      (node (ref "U$15") (pin "4") (pinfunction "2Y_4") (pintype "bidirectional"))
      (node (ref "U5") (pin "3") (pinfunction "DI_3") (pintype "bidirectional"))
    )
    (net (code "151") (name "Net-(U$15-3Y)") (class "Default")
      (node (ref "U$15") (pin "6") (pinfunction "3Y_6") (pintype "bidirectional"))
      (node (ref "U5") (pin "5") (pinfunction "SCK_5") (pintype "bidirectional"))
    )
    (net (code "152") (name "Net-(U1-A)") (class "Default")
      (node (ref "R13") (pin "1") (pinfunction "1_1") (pintype "passive"))
      (node (ref "U1") (pin "15") (pinfunction "A_15") (pintype "power_in"))
    )
    (net (code "153") (name "Net-(U1-K)") (class "Default")
      (node (ref "T4") (pin "C") (pinfunction "C_C") (pintype "passive"))
      (node (ref "U1") (pin "16") (pinfunction "K_16") (pintype "power_in"))
    )
    (net (code "154") (name "VCC") (class "Default")
      (node (ref "C28") (pin "+") (pinfunction "+_+") (pintype "passive"))
      (node (ref "IC1") (pin "1") (pinfunction "VIN_1") (pintype "power_in"))
      (node (ref "Q1") (pin "2") (pinfunction "S_2") (pintype "passive"))
      (node (ref "R36") (pin "1") (pinfunction "1_1") (pintype "passive"))
      (node (ref "U$4") (pin "VIN") (pinfunction "VIN_VIN") (pintype "power_in"))
    )
    (net (code "155") (name "unconnected-(H1-MOUNT-PadB3,2)") (class "Default")
      (node (ref "H1") (pin "B3,2") (pinfunction "MOUNT_B3,2") (pintype "passive"))
    )
    (net (code "156") (name "unconnected-(H2-MOUNT-PadB3,2)") (class "Default")
      (node (ref "H2") (pin "B3,2") (pinfunction "MOUNT_B3,2") (pintype "passive"))
    )
    (net (code "157") (name "unconnected-(H3-MOUNT-PadB3,2)") (class "Default")
      (node (ref "H3") (pin "B3,2") (pinfunction "MOUNT_B3,2") (pintype "passive"))
    )
    (net (code "158") (name "unconnected-(H4-MOUNT-PadB3,2)") (class "Default")
      (node (ref "H4") (pin "B3,2") (pinfunction "MOUNT_B3,2") (pintype "passive"))
    )
    (net (code "159") (name "unconnected-(H5-MOUNT-PadB3,2)") (class "Default")
      (node (ref "H5") (pin "B3,2") (pinfunction "MOUNT_B3,2") (pintype "passive"))
    )
    (net (code "160") (name "unconnected-(H6-MOUNT-PadB3,2)") (class "Default")
      (node (ref "H6") (pin "B3,2") (pinfunction "MOUNT_B3,2") (pintype "passive"))
    )
    (net (code "161") (name "unconnected-(IC4-GP0-Pad10)") (class "Default")
      (node (ref "IC4") (pin "10") (pinfunction "GP0_10") (pintype "bidirectional"))
    )
    (net (code "162") (name "unconnected-(IC4-INT-Pad8)") (class "Default")
      (node (ref "IC4") (pin "8") (pinfunction "INT_8") (pintype "output"))
    )
    (net (code "163") (name "unconnected-(IC6-DIG4-Pad3)") (class "Default")
      (node (ref "IC6") (pin "3") (pinfunction "DIG4_3") (pintype "output"))
    )
    (net (code "164") (name "unconnected-(IC6-DIG5-Pad10)") (class "Default")
      (node (ref "IC6") (pin "10") (pinfunction "DIG5_10") (pintype "output"))
    )
    (net (code "165") (name "unconnected-(IC6-DIG6-Pad5)") (class "Default")
      (node (ref "IC6") (pin "5") (pinfunction "DIG6_5") (pintype "output"))
    )
    (net (code "166") (name "unconnected-(IC6-DIG7-Pad8)") (class "Default")
      (node (ref "IC6") (pin "8") (pinfunction "DIG7_8") (pintype "output"))
    )
    (net (code "167") (name "unconnected-(IC6-DOUT-Pad24)") (class "Default")
      (node (ref "IC6") (pin "24") (pinfunction "DOUT_24") (pintype "output"))
    )
    (net (code "168") (name "unconnected-(JP8-Pad4)") (class "Default")
      (node (ref "JP8") (pin "4") (pinfunction "4_4") (pintype "passive"))
    )
    (net (code "169") (name "unconnected-(M1-IRQ-Pad8)") (class "Default")
      (node (ref "M1") (pin "8") (pinfunction "IRQ_8") (pintype "bidirectional"))
    )
    (net (code "170") (name "unconnected-(S9-O-Pad1)") (class "Default")
      (node (ref "S9") (pin "1") (pinfunction "O_1") (pintype "passive"))
    )
    (net (code "171") (name "unconnected-(U$4-PadRESERVED)") (class "Default")
      (node (ref "U$4") (pin "RESERVED") (pinfunction "RESERVED_RESERVED") (pintype "no_connect"))
    )
    (net (code "172") (name "unconnected-(U$6-+1-Pad+$2)") (class "Default")
      (node (ref "U$6") (pin "+$2") (pinfunction "+1_+$2") (pintype "passive"))
    )
    (net (code "173") (name "unconnected-(U$15-5Y-Pad12)") (class "Default")
      (node (ref "U$15") (pin "12") (pinfunction "5Y_12") (pintype "bidirectional"))
    )
    (net (code "174") (name "unconnected-(U$15-6Y-Pad15)") (class "Default")
      (node (ref "U$15") (pin "15") (pinfunction "6Y_15") (pintype "bidirectional"))
    )
    (net (code "175") (name "unconnected-(U1-DB0-Pad7)") (class "Default")
      (node (ref "U1") (pin "7") (pinfunction "DB0_7") (pintype "bidirectional"))
    )
    (net (code "176") (name "unconnected-(U1-DB1-Pad8)") (class "Default")
      (node (ref "U1") (pin "8") (pinfunction "DB1_8") (pintype "bidirectional"))
    )
    (net (code "177") (name "unconnected-(U1-DB2-Pad9)") (class "Default")
      (node (ref "U1") (pin "9") (pinfunction "DB2_9") (pintype "bidirectional"))
    )
    (net (code "178") (name "unconnected-(U1-DB3-Pad10)") (class "Default")
      (node (ref "U1") (pin "10") (pinfunction "DB3_10") (pintype "bidirectional"))
    )
    (net (code "179") (name "unconnected-(U5-NC-Pad1)") (class "Default")
      (node (ref "U5") (pin "1") (pinfunction "NC_1") (pintype "bidirectional"))
    )
    (net (code "180") (name "unconnected-(U5-RSV-Pad8)") (class "Default")
      (node (ref "U5") (pin "8") (pinfunction "RSV_8") (pintype "bidirectional"))
    )
  )
)
